# asbuilt.net
KiCad netlist of a schematic drawn in EAGLE
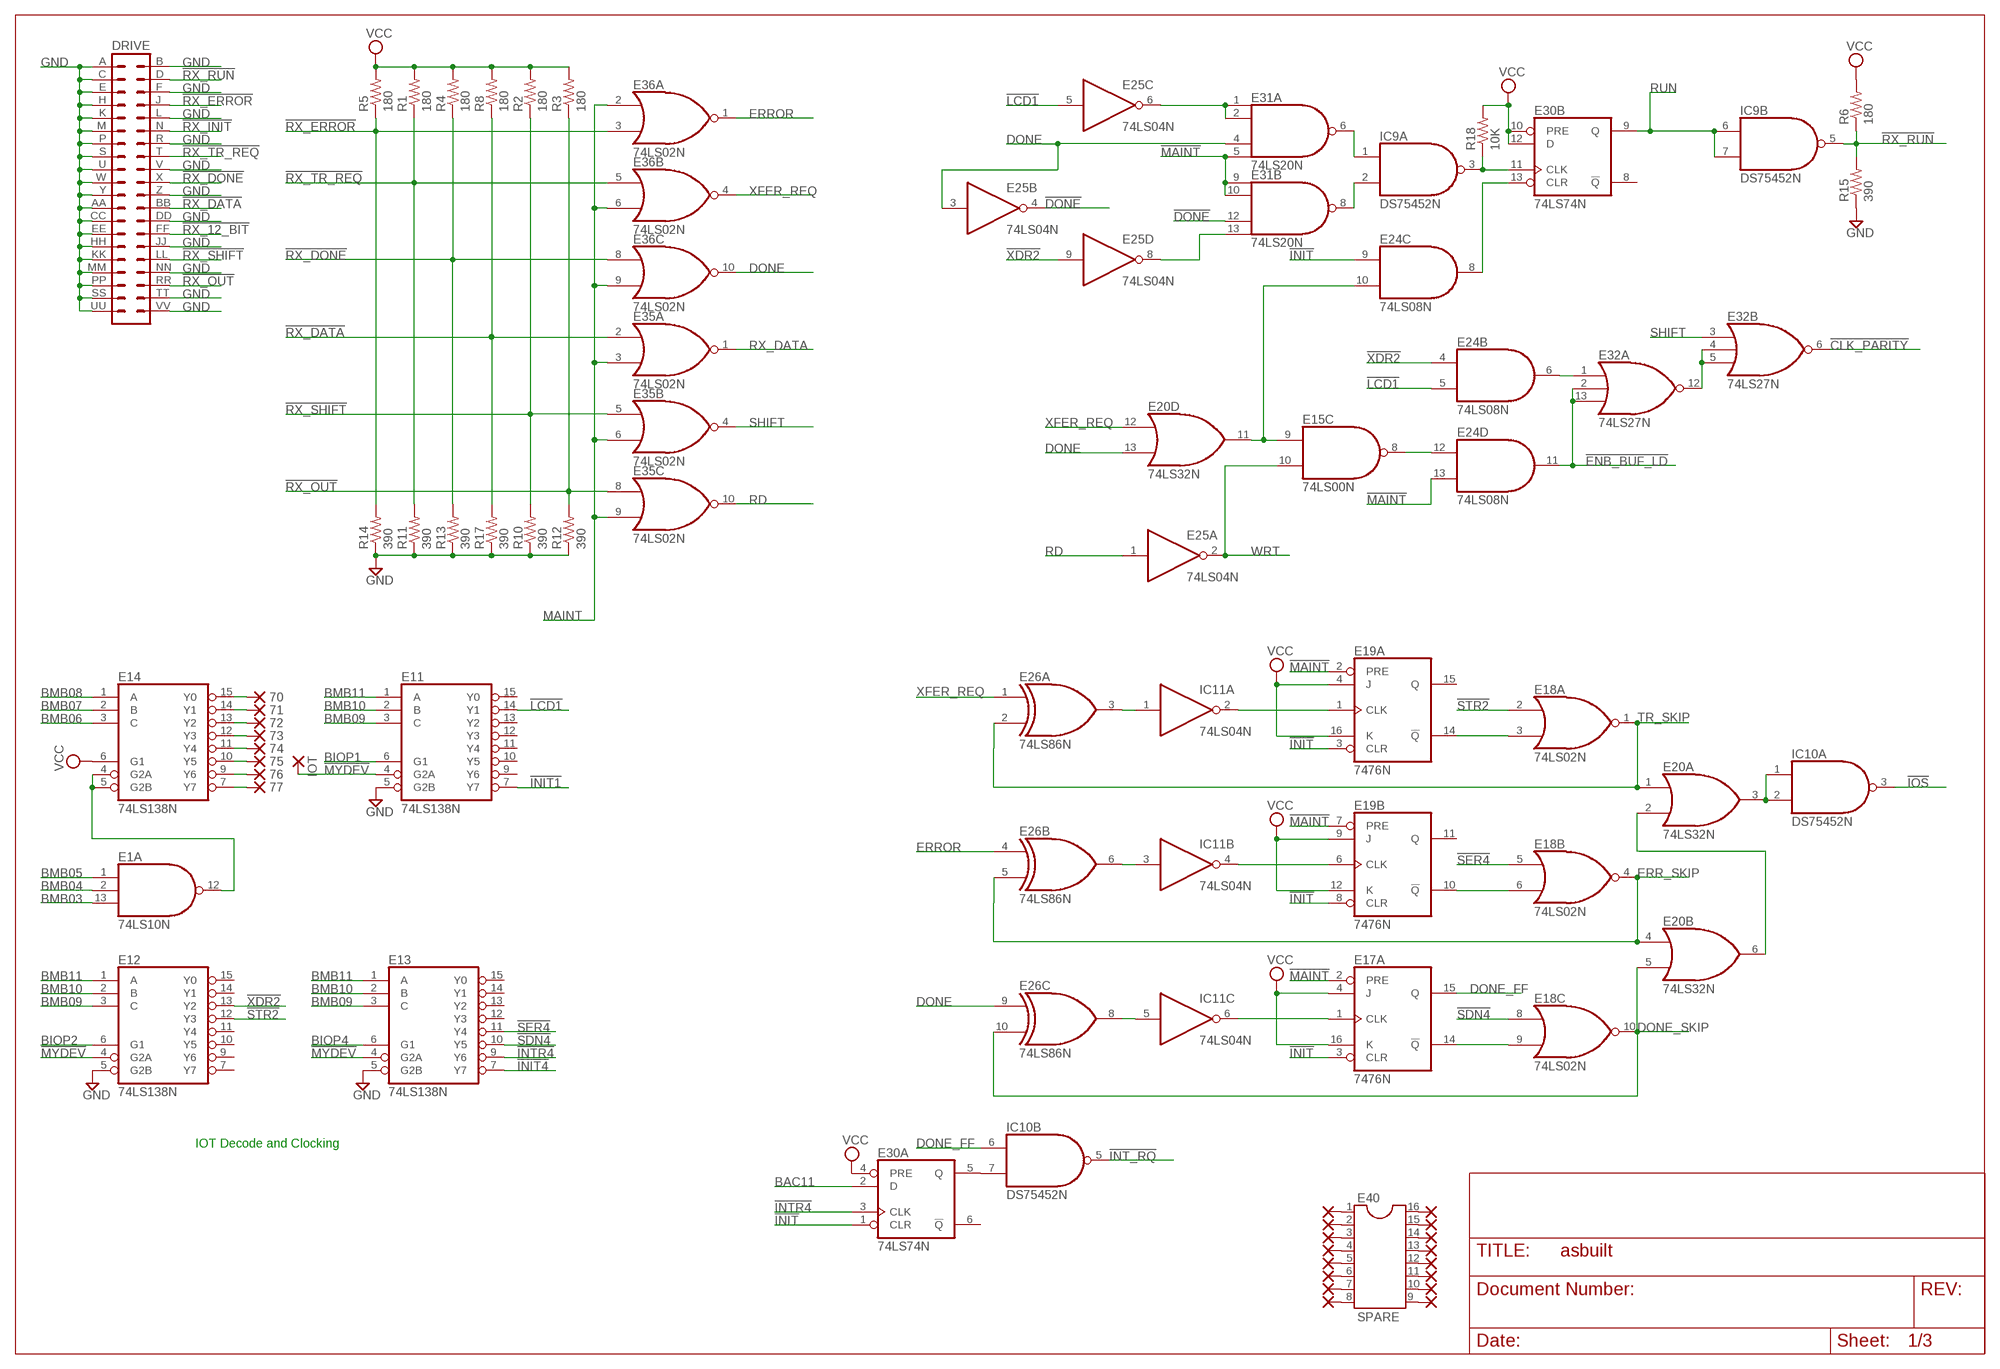
[diagram p0: schematic, sheet 1]
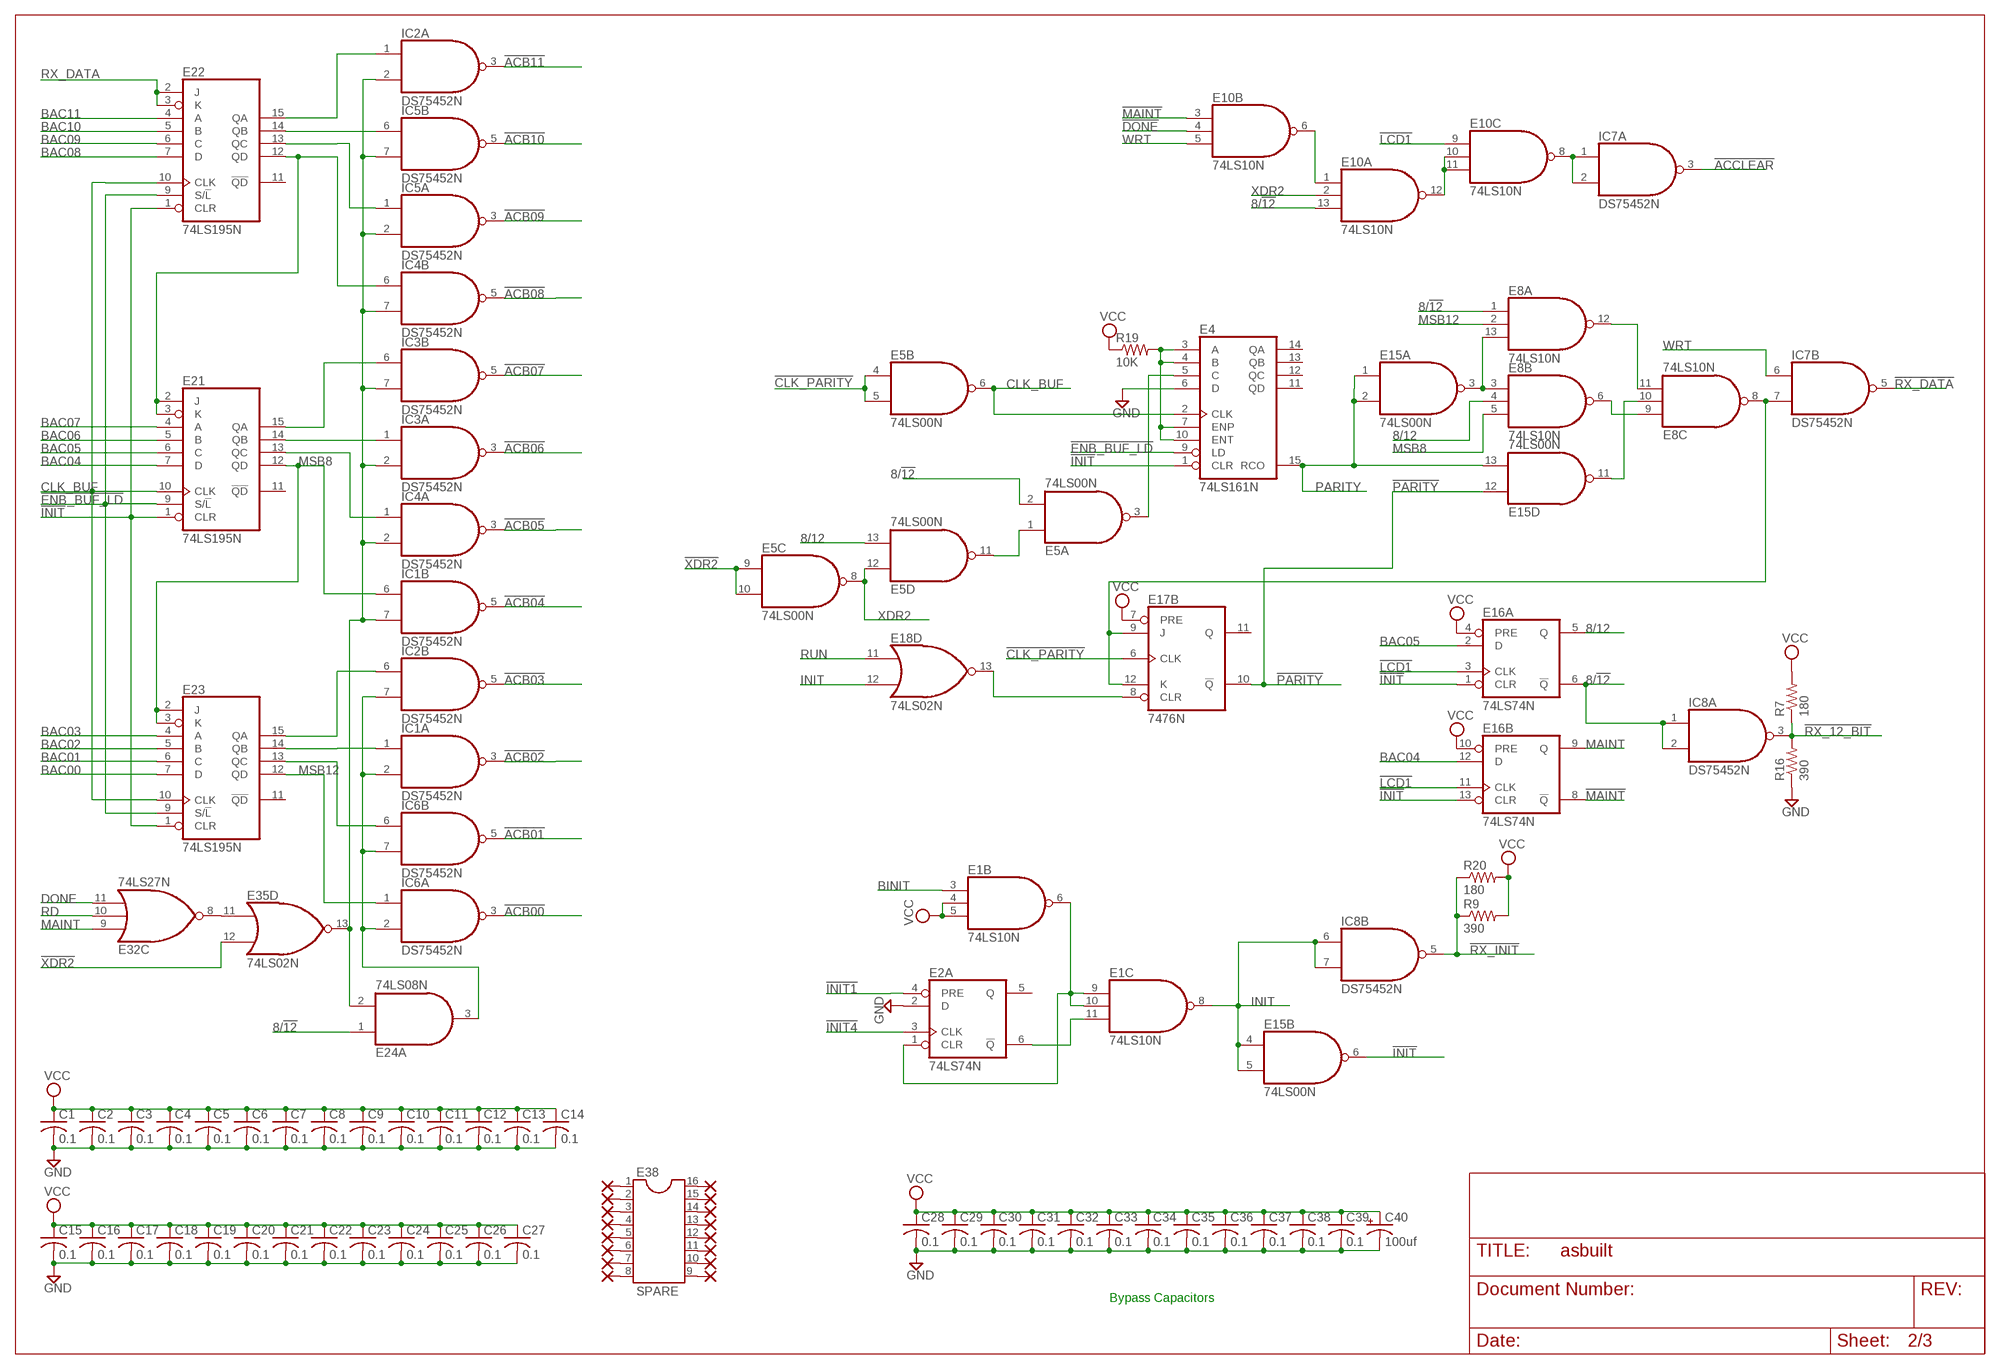
[diagram p1: schematic, sheet 2]
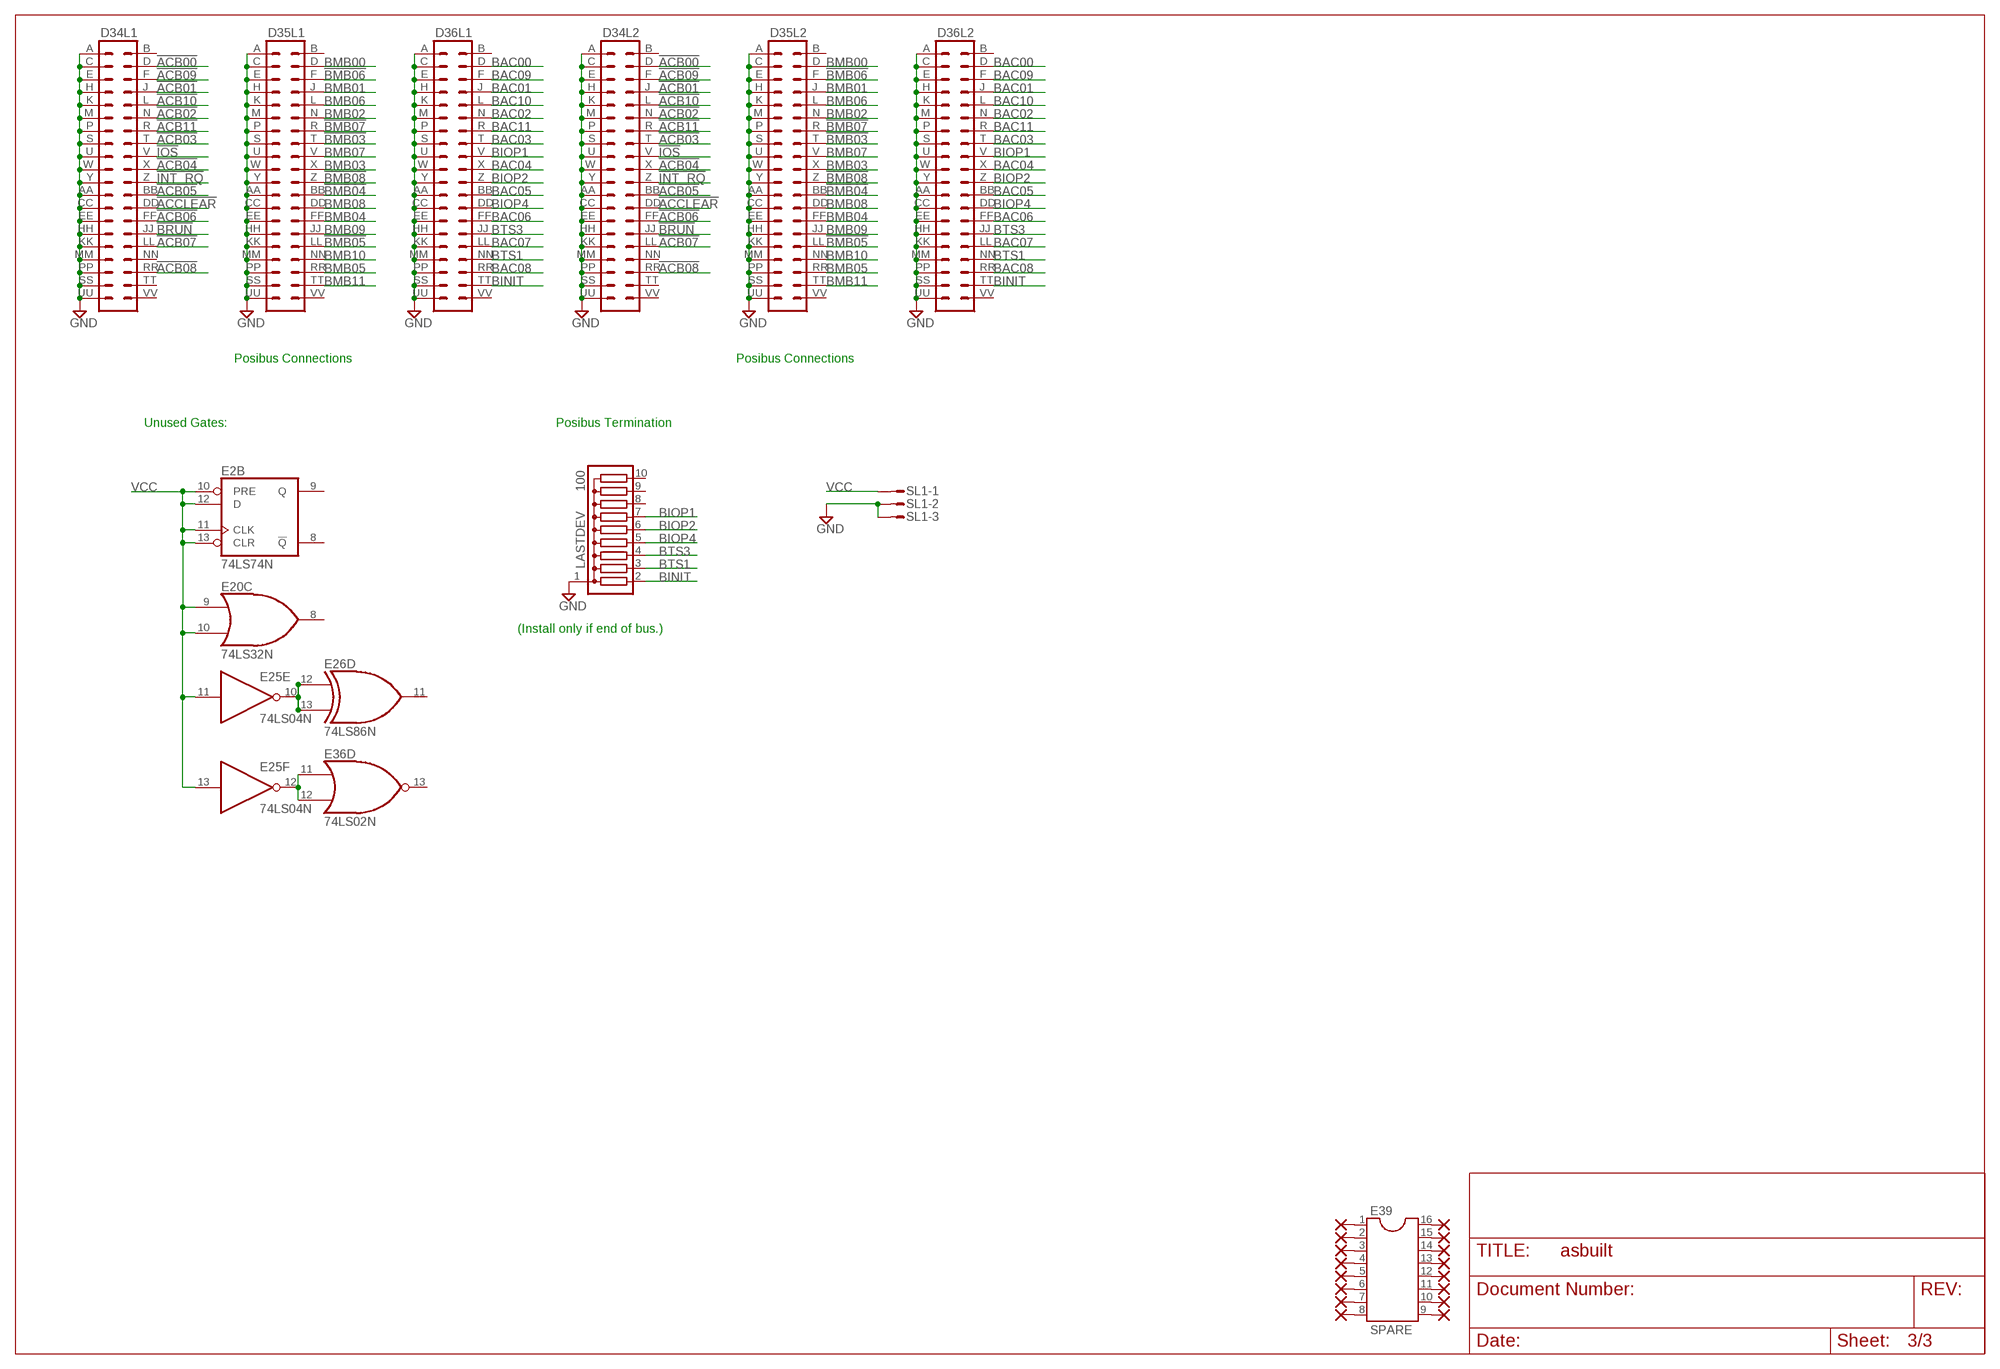
[diagram p2: schematic, sheet 3]

(export (version "E")
  (design (tool "Eeschema 10.0.6"))
  (components
    (comp (ref "C1")
      (value "0.1")
      (footprint "eagle-import:C050-025X075")
      (libsource (lib "eagle-import") (part "C-US050-025X075"))
    )
    (comp (ref "C2")
      (value "0.1")
      (footprint "eagle-import:C050-025X075")
      (libsource (lib "eagle-import") (part "C-US050-025X075"))
    )
    (comp (ref "C3")
      (value "0.1")
      (footprint "eagle-import:C050-025X075")
      (libsource (lib "eagle-import") (part "C-US050-025X075"))
    )
    (comp (ref "C4")
      (value "0.1")
      (footprint "eagle-import:C050-025X075")
      (libsource (lib "eagle-import") (part "C-US050-025X075"))
    )
    (comp (ref "C5")
      (value "0.1")
      (footprint "eagle-import:C050-025X075")
      (libsource (lib "eagle-import") (part "C-US050-025X075"))
    )
    (comp (ref "C6")
      (value "0.1")
      (footprint "eagle-import:C050-025X075")
      (libsource (lib "eagle-import") (part "C-US050-025X075"))
    )
    (comp (ref "C7")
      (value "0.1")
      (footprint "eagle-import:C050-025X075")
      (libsource (lib "eagle-import") (part "C-US050-025X075"))
    )
    (comp (ref "C8")
      (value "0.1")
      (footprint "eagle-import:C050-025X075")
      (libsource (lib "eagle-import") (part "C-US050-025X075"))
    )
    (comp (ref "C9")
      (value "0.1")
      (footprint "eagle-import:C050-025X075")
      (libsource (lib "eagle-import") (part "C-US050-025X075"))
    )
    (comp (ref "C10")
      (value "0.1")
      (footprint "eagle-import:C050-025X075")
      (libsource (lib "eagle-import") (part "C-US050-025X075"))
    )
    (comp (ref "C11")
      (value "0.1")
      (footprint "eagle-import:C050-025X075")
      (libsource (lib "eagle-import") (part "C-US050-025X075"))
    )
    (comp (ref "C12")
      (value "0.1")
      (footprint "eagle-import:C050-025X075")
      (libsource (lib "eagle-import") (part "C-US050-025X075"))
    )
    (comp (ref "C13")
      (value "0.1")
      (footprint "eagle-import:C050-025X075")
      (libsource (lib "eagle-import") (part "C-US050-025X075"))
    )
    (comp (ref "C14")
      (value "0.1")
      (footprint "eagle-import:C050-025X075")
      (libsource (lib "eagle-import") (part "C-US050-025X075"))
    )
    (comp (ref "C15")
      (value "0.1")
      (footprint "eagle-import:C050-025X075")
      (libsource (lib "eagle-import") (part "C-US050-025X075"))
    )
    (comp (ref "C16")
      (value "0.1")
      (footprint "eagle-import:C050-025X075")
      (libsource (lib "eagle-import") (part "C-US050-025X075"))
    )
    (comp (ref "C17")
      (value "0.1")
      (footprint "eagle-import:C050-025X075")
      (libsource (lib "eagle-import") (part "C-US050-025X075"))
    )
    (comp (ref "C18")
      (value "0.1")
      (footprint "eagle-import:C050-025X075")
      (libsource (lib "eagle-import") (part "C-US050-025X075"))
    )
    (comp (ref "C19")
      (value "0.1")
      (footprint "eagle-import:C050-025X075")
      (libsource (lib "eagle-import") (part "C-US050-025X075"))
    )
    (comp (ref "C20")
      (value "0.1")
      (footprint "eagle-import:C050-025X075")
      (libsource (lib "eagle-import") (part "C-US050-025X075"))
    )
    (comp (ref "C21")
      (value "0.1")
      (footprint "eagle-import:C050-025X075")
      (libsource (lib "eagle-import") (part "C-US050-025X075"))
    )
    (comp (ref "C22")
      (value "0.1")
      (footprint "eagle-import:C050-025X075")
      (libsource (lib "eagle-import") (part "C-US050-025X075"))
    )
    (comp (ref "C23")
      (value "0.1")
      (footprint "eagle-import:C050-025X075")
      (libsource (lib "eagle-import") (part "C-US050-025X075"))
    )
    (comp (ref "C24")
      (value "0.1")
      (footprint "eagle-import:C050-025X075")
      (libsource (lib "eagle-import") (part "C-US050-025X075"))
    )
    (comp (ref "C25")
      (value "0.1")
      (footprint "eagle-import:C050-025X075")
      (libsource (lib "eagle-import") (part "C-US050-025X075"))
    )
    (comp (ref "C26")
      (value "0.1")
      (footprint "eagle-import:C050-025X075")
      (libsource (lib "eagle-import") (part "C-US050-025X075"))
    )
    (comp (ref "C27")
      (value "0.1")
      (footprint "eagle-import:C050-025X075")
      (libsource (lib "eagle-import") (part "C-US050-025X075"))
    )
    (comp (ref "C28")
      (value "0.1")
      (footprint "eagle-import:C050-025X075")
      (libsource (lib "eagle-import") (part "C-US050-025X075"))
    )
    (comp (ref "C29")
      (value "0.1")
      (footprint "eagle-import:C050-025X075")
      (libsource (lib "eagle-import") (part "C-US050-025X075"))
    )
    (comp (ref "C30")
      (value "0.1")
      (footprint "eagle-import:C050-025X075")
      (libsource (lib "eagle-import") (part "C-US050-025X075"))
    )
    (comp (ref "C31")
      (value "0.1")
      (footprint "eagle-import:C050-025X075")
      (libsource (lib "eagle-import") (part "C-US050-025X075"))
    )
    (comp (ref "C32")
      (value "0.1")
      (footprint "eagle-import:C050-025X075")
      (libsource (lib "eagle-import") (part "C-US050-025X075"))
    )
    (comp (ref "C33")
      (value "0.1")
      (footprint "eagle-import:C050-025X075")
      (libsource (lib "eagle-import") (part "C-US050-025X075"))
    )
    (comp (ref "C34")
      (value "0.1")
      (footprint "eagle-import:C050-025X075")
      (libsource (lib "eagle-import") (part "C-US050-025X075"))
    )
    (comp (ref "C35")
      (value "0.1")
      (footprint "eagle-import:C050-025X075")
      (libsource (lib "eagle-import") (part "C-US050-025X075"))
    )
    (comp (ref "C36")
      (value "0.1")
      (footprint "eagle-import:C050-025X075")
      (libsource (lib "eagle-import") (part "C-US050-025X075"))
    )
    (comp (ref "C37")
      (value "0.1")
      (footprint "eagle-import:C050-025X075")
      (libsource (lib "eagle-import") (part "C-US050-025X075"))
    )
    (comp (ref "C38")
      (value "0.1")
      (footprint "eagle-import:C050-025X075")
      (libsource (lib "eagle-import") (part "C-US050-025X075"))
    )
    (comp (ref "C39")
      (value "0.1")
      (footprint "eagle-import:C050-025X075")
      (libsource (lib "eagle-import") (part "C-US050-025X075"))
    )
    (comp (ref "C40")
      (value "100uf")
      (footprint "eagle-import:E22-9")
      (libsource (lib "eagle-import") (part "CPOL-USE22-9AXIAL"))
    )
    (comp (ref "E1")
      (value "74LS10N")
      (footprint "eagle-import:DIL14")
      (libsource (lib "eagle-import") (part "7410NLS"))
    )
    (comp (ref "E2")
      (value "74LS74N")
      (footprint "eagle-import:DIL14")
      (libsource (lib "eagle-import") (part "7474NLS"))
    )
    (comp (ref "E4")
      (value "74LS161N")
      (footprint "eagle-import:DIL16")
      (libsource (lib "eagle-import") (part "74161NLS"))
    )
    (comp (ref "E5")
      (value "74LS00N")
      (footprint "eagle-import:DIL14")
      (libsource (lib "eagle-import") (part "7400NLS"))
    )
    (comp (ref "E8")
      (value "74LS10N")
      (footprint "eagle-import:DIL14")
      (libsource (lib "eagle-import") (part "7410NLS"))
    )
    (comp (ref "E10")
      (value "74LS10N")
      (footprint "eagle-import:DIL14")
      (libsource (lib "eagle-import") (part "7410NLS"))
    )
    (comp (ref "E15")
      (value "74LS00N")
      (footprint "eagle-import:DIL14")
      (libsource (lib "eagle-import") (part "7400NLS"))
    )
    (comp (ref "E16")
      (value "74LS74N")
      (footprint "eagle-import:DIL14")
      (libsource (lib "eagle-import") (part "7474NLS"))
    )
    (comp (ref "E17")
      (value "7476N")
      (footprint "eagle-import:DIL16")
      (libsource (lib "eagle-import") (part "7476N"))
    )
    (comp (ref "E18")
      (value "74LS02N")
      (footprint "eagle-import:DIL14")
      (libsource (lib "eagle-import") (part "7402NLS"))
    )
    (comp (ref "E21")
      (value "74LS195N")
      (footprint "eagle-import:DIL16")
      (libsource (lib "eagle-import") (part "74195NLS"))
    )
    (comp (ref "E22")
      (value "74LS195N")
      (footprint "eagle-import:DIL16")
      (libsource (lib "eagle-import") (part "74195NLS"))
    )
    (comp (ref "E23")
      (value "74LS195N")
      (footprint "eagle-import:DIL16")
      (libsource (lib "eagle-import") (part "74195NLS"))
    )
    (comp (ref "E24")
      (value "74LS08N")
      (footprint "eagle-import:DIL14")
      (libsource (lib "eagle-import") (part "7408NLS"))
    )
    (comp (ref "E32")
      (value "74LS27N")
      (footprint "eagle-import:DIL14")
      (libsource (lib "eagle-import") (part "7427NLS"))
    )
    (comp (ref "E35")
      (value "74LS02N")
      (footprint "eagle-import:DIL14")
      (libsource (lib "eagle-import") (part "7402NLS"))
    )
    (comp (ref "E38")
      (value "SPARE")
      (footprint "eagle-import:DIL16")
      (libsource (lib "eagle-import") (part "DIL16"))
    )
    (comp (ref "IC1")
      (value "DS75452N")
      (footprint "eagle-import:DIL08")
      (libsource (lib "eagle-import") (part "DS75452N"))
    )
    (comp (ref "IC2")
      (value "DS75452N")
      (footprint "eagle-import:DIL08")
      (libsource (lib "eagle-import") (part "DS75452N"))
    )
    (comp (ref "IC3")
      (value "DS75452N")
      (footprint "eagle-import:DIL08")
      (libsource (lib "eagle-import") (part "DS75452N"))
    )
    (comp (ref "IC4")
      (value "DS75452N")
      (footprint "eagle-import:DIL08")
      (libsource (lib "eagle-import") (part "DS75452N"))
    )
    (comp (ref "IC5")
      (value "DS75452N")
      (footprint "eagle-import:DIL08")
      (libsource (lib "eagle-import") (part "DS75452N"))
    )
    (comp (ref "IC6")
      (value "DS75452N")
      (footprint "eagle-import:DIL08")
      (libsource (lib "eagle-import") (part "DS75452N"))
    )
    (comp (ref "IC7")
      (value "DS75452N")
      (footprint "eagle-import:DIL08")
      (libsource (lib "eagle-import") (part "DS75452N"))
    )
    (comp (ref "IC8")
      (value "DS75452N")
      (footprint "eagle-import:DIL08")
      (libsource (lib "eagle-import") (part "DS75452N"))
    )
    (comp (ref "PAD10")
      (value "1,6/0,8")
      (footprint "eagle-import:1,6_0,8")
      (libsource (lib "eagle-import") (part "1,6/0,8"))
    )
    (comp (ref "PAD11")
      (value "1,6/0,8")
      (footprint "eagle-import:1,6_0,8")
      (libsource (lib "eagle-import") (part "1,6/0,8"))
    )
    (comp (ref "PAD12")
      (value "1,6/0,8")
      (footprint "eagle-import:1,6_0,8")
      (libsource (lib "eagle-import") (part "1,6/0,8"))
    )
    (comp (ref "PAD13")
      (value "1,6/0,8")
      (footprint "eagle-import:1,6_0,8")
      (libsource (lib "eagle-import") (part "1,6/0,8"))
    )
    (comp (ref "PAD14")
      (value "1,6/0,8")
      (footprint "eagle-import:1,6_0,8")
      (libsource (lib "eagle-import") (part "1,6/0,8"))
    )
    (comp (ref "PAD15")
      (value "1,6/0,8")
      (footprint "eagle-import:1,6_0,8")
      (libsource (lib "eagle-import") (part "1,6/0,8"))
    )
    (comp (ref "PAD16")
      (value "1,6/0,8")
      (footprint "eagle-import:1,6_0,8")
      (libsource (lib "eagle-import") (part "1,6/0,8"))
    )
    (comp (ref "PAD17")
      (value "1,6/0,8")
      (footprint "eagle-import:1,6_0,8")
      (libsource (lib "eagle-import") (part "1,6/0,8"))
    )
    (comp (ref "PAD20")
      (value "1,6/0,8")
      (footprint "eagle-import:1,6_0,8")
      (libsource (lib "eagle-import") (part "1,6/0,8"))
    )
    (comp (ref "PAD21")
      (value "1,6/0,8")
      (footprint "eagle-import:1,6_0,8")
      (libsource (lib "eagle-import") (part "1,6/0,8"))
    )
    (comp (ref "PAD22")
      (value "1,6/0,8")
      (footprint "eagle-import:1,6_0,8")
      (libsource (lib "eagle-import") (part "1,6/0,8"))
    )
    (comp (ref "PAD23")
      (value "1,6/0,8")
      (footprint "eagle-import:1,6_0,8")
      (libsource (lib "eagle-import") (part "1,6/0,8"))
    )
    (comp (ref "PAD24")
      (value "1,6/0,8")
      (footprint "eagle-import:1,6_0,8")
      (libsource (lib "eagle-import") (part "1,6/0,8"))
    )
    (comp (ref "PAD25")
      (value "1,6/0,8")
      (footprint "eagle-import:1,6_0,8")
      (libsource (lib "eagle-import") (part "1,6/0,8"))
    )
    (comp (ref "PAD26")
      (value "1,6/0,8")
      (footprint "eagle-import:1,6_0,8")
      (libsource (lib "eagle-import") (part "1,6/0,8"))
    )
    (comp (ref "PAD27")
      (value "1,6/0,8")
      (footprint "eagle-import:1,6_0,8")
      (libsource (lib "eagle-import") (part "1,6/0,8"))
    )
    (comp (ref "R7")
      (value "180")
      (footprint "eagle-import:0207_10")
      (libsource (lib "eagle-import") (part "R-US_0207/10"))
    )
    (comp (ref "R9")
      (value "390")
      (footprint "eagle-import:0207_10")
      (libsource (lib "eagle-import") (part "R-US_0207/10"))
    )
    (comp (ref "R16")
      (value "390")
      (footprint "eagle-import:0207_10")
      (libsource (lib "eagle-import") (part "R-US_0207/10"))
    )
    (comp (ref "R19")
      (value "10K")
      (footprint "eagle-import:0207_10")
      (libsource (lib "eagle-import") (part "R-US_0207/10"))
    )
    (comp (ref "R20")
      (value "180")
      (footprint "eagle-import:0207_10")
      (libsource (lib "eagle-import") (part "R-US_0207/10"))
    )
    (comp (ref "D34L1")
      (value "DEC40PINV")
      (footprint "eagle-import:DEC40PINV")
      (libsource (lib "eagle-import") (part "DEC40PINV"))
    )
    (comp (ref "D34L2")
      (value "DEC40PINV")
      (footprint "eagle-import:DEC40PINV")
      (libsource (lib "eagle-import") (part "DEC40PINV"))
    )
    (comp (ref "D35L1")
      (value "DEC40PINV")
      (footprint "eagle-import:DEC40PINV")
      (libsource (lib "eagle-import") (part "DEC40PINV"))
    )
    (comp (ref "D35L2")
      (value "DEC40PINV")
      (footprint "eagle-import:DEC40PINV")
      (libsource (lib "eagle-import") (part "DEC40PINV"))
    )
    (comp (ref "D36L1")
      (value "DEC40PINV")
      (footprint "eagle-import:DEC40PINV")
      (libsource (lib "eagle-import") (part "DEC40PINV"))
    )
    (comp (ref "D36L2")
      (value "DEC40PINV")
      (footprint "eagle-import:DEC40PINV")
      (libsource (lib "eagle-import") (part "DEC40PINV"))
    )
    (comp (ref "E20")
      (value "74LS32N")
      (footprint "eagle-import:DIL14")
      (libsource (lib "eagle-import") (part "7432NLS"))
    )
    (comp (ref "E25")
      (value "74LS04N")
      (footprint "eagle-import:DIL14")
      (libsource (lib "eagle-import") (part "7404NLS"))
    )
    (comp (ref "E26")
      (value "74LS86N")
      (footprint "eagle-import:DIL14")
      (libsource (lib "eagle-import") (part "7486NLS"))
    )
    (comp (ref "E36")
      (value "74LS02N")
      (footprint "eagle-import:DIL14")
      (libsource (lib "eagle-import") (part "7402NLS"))
    )
    (comp (ref "E39")
      (value "SPARE")
      (footprint "eagle-import:DIL16")
      (libsource (lib "eagle-import") (part "DIL16"))
    )
    (comp (ref "LASTDEV")
      (value "100")
      (footprint "eagle-import:SIL10")
      (libsource (lib "eagle-import") (part "G09R"))
    )
    (comp (ref "PAD42")
      (value "1,6/0,8")
      (footprint "eagle-import:1,6_0,8")
      (libsource (lib "eagle-import") (part "1,6/0,8"))
    )
    (comp (ref "PAD43")
      (value "1,6/0,8")
      (footprint "eagle-import:1,6_0,8")
      (libsource (lib "eagle-import") (part "1,6/0,8"))
    )
    (comp (ref "PAD44")
      (value "1,6/0,8")
      (footprint "eagle-import:1,6_0,8")
      (libsource (lib "eagle-import") (part "1,6/0,8"))
    )
    (comp (ref "PAD45")
      (value "1,6/0,8")
      (footprint "eagle-import:1,6_0,8")
      (libsource (lib "eagle-import") (part "1,6/0,8"))
    )
    (comp (ref "PAD46")
      (value "1,6/0,8")
      (footprint "eagle-import:1,6_0,8")
      (libsource (lib "eagle-import") (part "1,6/0,8"))
    )
    (comp (ref "PAD47")
      (value "1,6/0,8")
      (footprint "eagle-import:1,6_0,8")
      (libsource (lib "eagle-import") (part "1,6/0,8"))
    )
    (comp (ref "PAD48")
      (value "1,6/0,8")
      (footprint "eagle-import:1,6_0,8")
      (libsource (lib "eagle-import") (part "1,6/0,8"))
    )
    (comp (ref "PAD49")
      (value "1,6/0,8")
      (footprint "eagle-import:1,6_0,8")
      (libsource (lib "eagle-import") (part "1,6/0,8"))
    )
    (comp (ref "PAD50")
      (value "1,6/0,8")
      (footprint "eagle-import:1,6_0,8")
      (libsource (lib "eagle-import") (part "1,6/0,8"))
    )
    (comp (ref "PAD51")
      (value "1,6/0,8")
      (footprint "eagle-import:1,6_0,8")
      (libsource (lib "eagle-import") (part "1,6/0,8"))
    )
    (comp (ref "PAD52")
      (value "1,6/0,8")
      (footprint "eagle-import:1,6_0,8")
      (libsource (lib "eagle-import") (part "1,6/0,8"))
    )
    (comp (ref "PAD53")
      (value "1,6/0,8")
      (footprint "eagle-import:1,6_0,8")
      (libsource (lib "eagle-import") (part "1,6/0,8"))
    )
    (comp (ref "PAD54")
      (value "1,6/0,8")
      (footprint "eagle-import:1,6_0,8")
      (libsource (lib "eagle-import") (part "1,6/0,8"))
    )
    (comp (ref "PAD55")
      (value "1,6/0,8")
      (footprint "eagle-import:1,6_0,8")
      (libsource (lib "eagle-import") (part "1,6/0,8"))
    )
    (comp (ref "PAD56")
      (value "1,6/0,8")
      (footprint "eagle-import:1,6_0,8")
      (libsource (lib "eagle-import") (part "1,6/0,8"))
    )
    (comp (ref "PAD57")
      (value "1,6/0,8")
      (footprint "eagle-import:1,6_0,8")
      (libsource (lib "eagle-import") (part "1,6/0,8"))
    )
    (comp (ref "SL1")
      (value "MA04S")
      (footprint "eagle-import:04PA")
      (libsource (lib "eagle-import") (part "MA04S"))
    )
    (comp (ref "70")
      (value "1,6/0,8")
      (footprint "eagle-import:1,6_0,8")
      (libsource (lib "eagle-import") (part "1,6/0,8"))
    )
    (comp (ref "71")
      (value "1,6/0,8")
      (footprint "eagle-import:1,6_0,8")
      (libsource (lib "eagle-import") (part "1,6/0,8"))
    )
    (comp (ref "72")
      (value "1,6/0,8")
      (footprint "eagle-import:1,6_0,8")
      (libsource (lib "eagle-import") (part "1,6/0,8"))
    )
    (comp (ref "73")
      (value "1,6/0,8")
      (footprint "eagle-import:1,6_0,8")
      (libsource (lib "eagle-import") (part "1,6/0,8"))
    )
    (comp (ref "74")
      (value "1,6/0,8")
      (footprint "eagle-import:1,6_0,8")
      (libsource (lib "eagle-import") (part "1,6/0,8"))
    )
    (comp (ref "75")
      (value "1,6/0,8")
      (footprint "eagle-import:1,6_0,8")
      (libsource (lib "eagle-import") (part "1,6/0,8"))
    )
    (comp (ref "76")
      (value "1,6/0,8")
      (footprint "eagle-import:1,6_0,8")
      (libsource (lib "eagle-import") (part "1,6/0,8"))
    )
    (comp (ref "77")
      (value "1,6/0,8")
      (footprint "eagle-import:1,6_0,8")
      (libsource (lib "eagle-import") (part "1,6/0,8"))
    )
    (comp (ref "DRIVE")
      (value "DEC40PINV")
      (footprint "eagle-import:DEC40PINV")
      (libsource (lib "eagle-import") (part "DEC40PINV"))
    )
    (comp (ref "E11")
      (value "74LS138N")
      (footprint "eagle-import:DIL16")
      (libsource (lib "eagle-import") (part "74138NLS"))
    )
    (comp (ref "E12")
      (value "74LS138N")
      (footprint "eagle-import:DIL16")
      (libsource (lib "eagle-import") (part "74138NLS"))
    )
    (comp (ref "E13")
      (value "74LS138N")
      (footprint "eagle-import:DIL16")
      (libsource (lib "eagle-import") (part "74138NLS"))
    )
    (comp (ref "E14")
      (value "74LS138N")
      (footprint "eagle-import:DIL16")
      (libsource (lib "eagle-import") (part "74138NLS"))
    )
    (comp (ref "E19")
      (value "7476N")
      (footprint "eagle-import:DIL16")
      (libsource (lib "eagle-import") (part "7476N"))
    )
    (comp (ref "E30")
      (value "74LS74N")
      (footprint "eagle-import:DIL14")
      (libsource (lib "eagle-import") (part "7474NLS"))
    )
    (comp (ref "E31")
      (value "74LS20N")
      (footprint "eagle-import:DIL14")
      (libsource (lib "eagle-import") (part "7420NLS"))
    )
    (comp (ref "E40")
      (value "SPARE")
      (footprint "eagle-import:DIL16")
      (libsource (lib "eagle-import") (part "DIL16"))
    )
    (comp (ref "IC9")
      (value "DS75452N")
      (footprint "eagle-import:DIL08")
      (libsource (lib "eagle-import") (part "DS75452N"))
    )
    (comp (ref "IC10")
      (value "DS75452N")
      (footprint "eagle-import:DIL08")
      (libsource (lib "eagle-import") (part "DS75452N"))
    )
    (comp (ref "IC11")
      (value "74LS04N")
      (footprint "eagle-import:DIL14")
      (libsource (lib "eagle-import") (part "7404NLS"))
    )
    (comp (ref "IOT")
      (value "1,6/0,8")
      (footprint "eagle-import:1,6_0,8")
      (libsource (lib "eagle-import") (part "1,6/0,8"))
    )
    (comp (ref "PAD18")
      (value "1,6/0,8")
      (footprint "eagle-import:1,6_0,8")
      (libsource (lib "eagle-import") (part "1,6/0,8"))
    )
    (comp (ref "PAD19")
      (value "1,6/0,8")
      (footprint "eagle-import:1,6_0,8")
      (libsource (lib "eagle-import") (part "1,6/0,8"))
    )
    (comp (ref "PAD28")
      (value "1,6/0,8")
      (footprint "eagle-import:1,6_0,8")
      (libsource (lib "eagle-import") (part "1,6/0,8"))
    )
    (comp (ref "PAD29")
      (value "1,6/0,8")
      (footprint "eagle-import:1,6_0,8")
      (libsource (lib "eagle-import") (part "1,6/0,8"))
    )
    (comp (ref "PAD30")
      (value "1,6/0,8")
      (footprint "eagle-import:1,6_0,8")
      (libsource (lib "eagle-import") (part "1,6/0,8"))
    )
    (comp (ref "PAD31")
      (value "1,6/0,8")
      (footprint "eagle-import:1,6_0,8")
      (libsource (lib "eagle-import") (part "1,6/0,8"))
    )
    (comp (ref "PAD32")
      (value "1,6/0,8")
      (footprint "eagle-import:1,6_0,8")
      (libsource (lib "eagle-import") (part "1,6/0,8"))
    )
    (comp (ref "PAD33")
      (value "1,6/0,8")
      (footprint "eagle-import:1,6_0,8")
      (libsource (lib "eagle-import") (part "1,6/0,8"))
    )
    (comp (ref "PAD34")
      (value "1,6/0,8")
      (footprint "eagle-import:1,6_0,8")
      (libsource (lib "eagle-import") (part "1,6/0,8"))
    )
    (comp (ref "PAD35")
      (value "1,6/0,8")
      (footprint "eagle-import:1,6_0,8")
      (libsource (lib "eagle-import") (part "1,6/0,8"))
    )
    (comp (ref "PAD36")
      (value "1,6/0,8")
      (footprint "eagle-import:1,6_0,8")
      (libsource (lib "eagle-import") (part "1,6/0,8"))
    )
    (comp (ref "PAD37")
      (value "1,6/0,8")
      (footprint "eagle-import:1,6_0,8")
      (libsource (lib "eagle-import") (part "1,6/0,8"))
    )
    (comp (ref "PAD38")
      (value "1,6/0,8")
      (footprint "eagle-import:1,6_0,8")
      (libsource (lib "eagle-import") (part "1,6/0,8"))
    )
    (comp (ref "PAD39")
      (value "1,6/0,8")
      (footprint "eagle-import:1,6_0,8")
      (libsource (lib "eagle-import") (part "1,6/0,8"))
    )
    (comp (ref "PAD40")
      (value "1,6/0,8")
      (footprint "eagle-import:1,6_0,8")
      (libsource (lib "eagle-import") (part "1,6/0,8"))
    )
    (comp (ref "PAD41")
      (value "1,6/0,8")
      (footprint "eagle-import:1,6_0,8")
      (libsource (lib "eagle-import") (part "1,6/0,8"))
    )
    (comp (ref "R1")
      (value "180")
      (footprint "eagle-import:0207_10")
      (libsource (lib "eagle-import") (part "R-US_0207/10"))
    )
    (comp (ref "R2")
      (value "180")
      (footprint "eagle-import:0207_10")
      (libsource (lib "eagle-import") (part "R-US_0207/10"))
    )
    (comp (ref "R3")
      (value "180")
      (footprint "eagle-import:0207_10")
      (libsource (lib "eagle-import") (part "R-US_0207/10"))
    )
    (comp (ref "R4")
      (value "180")
      (footprint "eagle-import:0207_10")
      (libsource (lib "eagle-import") (part "R-US_0207/10"))
    )
    (comp (ref "R5")
      (value "180")
      (footprint "eagle-import:0207_10")
      (libsource (lib "eagle-import") (part "R-US_0207/10"))
    )
    (comp (ref "R6")
      (value "180")
      (footprint "eagle-import:0207_10")
      (libsource (lib "eagle-import") (part "R-US_0207/10"))
    )
    (comp (ref "R8")
      (value "180")
      (footprint "eagle-import:0207_10")
      (libsource (lib "eagle-import") (part "R-US_0207/10"))
    )
    (comp (ref "R10")
      (value "390")
      (footprint "eagle-import:0207_10")
      (libsource (lib "eagle-import") (part "R-US_0207/10"))
    )
    (comp (ref "R11")
      (value "390")
      (footprint "eagle-import:0207_10")
      (libsource (lib "eagle-import") (part "R-US_0207/10"))
    )
    (comp (ref "R12")
      (value "390")
      (footprint "eagle-import:0207_10")
      (libsource (lib "eagle-import") (part "R-US_0207/10"))
    )
    (comp (ref "R13")
      (value "390")
      (footprint "eagle-import:0207_10")
      (libsource (lib "eagle-import") (part "R-US_0207/10"))
    )
    (comp (ref "R14")
      (value "390")
      (footprint "eagle-import:0207_10")
      (libsource (lib "eagle-import") (part "R-US_0207/10"))
    )
    (comp (ref "R15")
      (value "390")
      (footprint "eagle-import:0207_10")
      (libsource (lib "eagle-import") (part "R-US_0207/10"))
    )
    (comp (ref "R17")
      (value "390")
      (footprint "eagle-import:0207_10")
      (libsource (lib "eagle-import") (part "R-US_0207/10"))
    )
    (comp (ref "R18")
      (value "10K")
      (footprint "eagle-import:0207_10")
      (libsource (lib "eagle-import") (part "R-US_0207/10"))
    )
  )
  (nets
    (net (code "1") (name "8{slash}12") (class "Default")
      (node (ref "E16") (pin "5") (pinfunction "Q_5") (pintype "output"))
      (node (ref "E5") (pin "13") (pinfunction "I1_13") (pintype "input"))
      (node (ref "E8") (pin "4") (pinfunction "I1_4") (pintype "input"))
    )
    (net (code "2") (name "8{slash}~{12}") (class "Default")
      (node (ref "E10") (pin "13") (pinfunction "I2_13") (pintype "input"))
      (node (ref "E16") (pin "6") (pinfunction "~{Q}_6") (pintype "output"))
      (node (ref "E24") (pin "1") (pinfunction "I0_1") (pintype "input"))
      (node (ref "E5") (pin "2") (pinfunction "I1_2") (pintype "input"))
      (node (ref "E8") (pin "1") (pinfunction "I0_1") (pintype "input"))
      (node (ref "IC8") (pin "1") (pinfunction "I0_1") (pintype "input"))
      (node (ref "IC8") (pin "2") (pinfunction "I1_2") (pintype "input"))
    )
    (net (code "3") (name "BAC00") (class "Default")
      (node (ref "D36L1") (pin "D") (pinfunction "4_D") (pintype "bidirectional"))
      (node (ref "D36L2") (pin "D") (pinfunction "4_D") (pintype "bidirectional"))
      (node (ref "E23") (pin "7") (pinfunction "D_7") (pintype "input"))
    )
    (net (code "4") (name "BAC01") (class "Default")
      (node (ref "D36L1") (pin "J") (pinfunction "8_J") (pintype "bidirectional"))
      (node (ref "D36L2") (pin "J") (pinfunction "8_J") (pintype "bidirectional"))
      (node (ref "E23") (pin "6") (pinfunction "C_6") (pintype "input"))
    )
    (net (code "5") (name "BAC02") (class "Default")
      (node (ref "D36L1") (pin "N") (pinfunction "12_N") (pintype "bidirectional"))
      (node (ref "D36L2") (pin "N") (pinfunction "12_N") (pintype "bidirectional"))
      (node (ref "E23") (pin "5") (pinfunction "B_5") (pintype "input"))
    )
    (net (code "6") (name "BAC03") (class "Default")
      (node (ref "D36L1") (pin "T") (pinfunction "16_T") (pintype "bidirectional"))
      (node (ref "D36L2") (pin "T") (pinfunction "16_T") (pintype "bidirectional"))
      (node (ref "E23") (pin "4") (pinfunction "A_4") (pintype "input"))
    )
    (net (code "7") (name "BAC04") (class "Default")
      (node (ref "D36L1") (pin "X") (pinfunction "20_X") (pintype "bidirectional"))
      (node (ref "D36L2") (pin "X") (pinfunction "20_X") (pintype "bidirectional"))
      (node (ref "E16") (pin "12") (pinfunction "D_12") (pintype "input"))
      (node (ref "E21") (pin "7") (pinfunction "D_7") (pintype "input"))
    )
    (net (code "8") (name "BAC05") (class "Default")
      (node (ref "D36L1") (pin "BB") (pinfunction "24_BB") (pintype "bidirectional"))
      (node (ref "D36L2") (pin "BB") (pinfunction "24_BB") (pintype "bidirectional"))
      (node (ref "E16") (pin "2") (pinfunction "D_2") (pintype "input"))
      (node (ref "E21") (pin "6") (pinfunction "C_6") (pintype "input"))
    )
    (net (code "9") (name "BAC06") (class "Default")
      (node (ref "D36L1") (pin "FF") (pinfunction "28_FF") (pintype "bidirectional"))
      (node (ref "D36L2") (pin "FF") (pinfunction "28_FF") (pintype "bidirectional"))
      (node (ref "E21") (pin "5") (pinfunction "B_5") (pintype "input"))
    )
    (net (code "10") (name "BAC07") (class "Default")
      (node (ref "D36L1") (pin "LL") (pinfunction "32_LL") (pintype "bidirectional"))
      (node (ref "D36L2") (pin "LL") (pinfunction "32_LL") (pintype "bidirectional"))
      (node (ref "E21") (pin "4") (pinfunction "A_4") (pintype "input"))
    )
    (net (code "11") (name "BAC08") (class "Default")
      (node (ref "D36L1") (pin "RR") (pinfunction "36_RR") (pintype "bidirectional"))
      (node (ref "D36L2") (pin "RR") (pinfunction "36_RR") (pintype "bidirectional"))
      (node (ref "E22") (pin "7") (pinfunction "D_7") (pintype "input"))
    )
    (net (code "12") (name "BAC09") (class "Default")
      (node (ref "D36L1") (pin "F") (pinfunction "6_F") (pintype "bidirectional"))
      (node (ref "D36L2") (pin "F") (pinfunction "6_F") (pintype "bidirectional"))
      (node (ref "E22") (pin "6") (pinfunction "C_6") (pintype "input"))
    )
    (net (code "13") (name "BAC10") (class "Default")
      (node (ref "D36L1") (pin "L") (pinfunction "10_L") (pintype "bidirectional"))
      (node (ref "D36L2") (pin "L") (pinfunction "10_L") (pintype "bidirectional"))
      (node (ref "E22") (pin "5") (pinfunction "B_5") (pintype "input"))
    )
    (net (code "14") (name "BAC11") (class "Default")
      (node (ref "D36L1") (pin "R") (pinfunction "14_R") (pintype "bidirectional"))
      (node (ref "D36L2") (pin "R") (pinfunction "14_R") (pintype "bidirectional"))
      (node (ref "E22") (pin "4") (pinfunction "A_4") (pintype "input"))
      (node (ref "E30") (pin "2") (pinfunction "D_2") (pintype "input"))
    )
    (net (code "15") (name "BINIT") (class "Default")
      (node (ref "D36L1") (pin "TT") (pinfunction "38_TT") (pintype "bidirectional"))
      (node (ref "D36L2") (pin "TT") (pinfunction "38_TT") (pintype "bidirectional"))
      (node (ref "E1") (pin "3") (pinfunction "I0_3") (pintype "input"))
      (node (ref "LASTDEV") (pin "2") (pinfunction "2_2") (pintype "passive"))
    )
    (net (code "16") (name "BIOP1") (class "Default")
      (node (ref "D36L1") (pin "V") (pinfunction "18_V") (pintype "bidirectional"))
      (node (ref "D36L2") (pin "V") (pinfunction "18_V") (pintype "bidirectional"))
      (node (ref "E11") (pin "6") (pinfunction "G1_6") (pintype "input"))
      (node (ref "LASTDEV") (pin "7") (pinfunction "7_7") (pintype "passive"))
    )
    (net (code "17") (name "BIOP2") (class "Default")
      (node (ref "D36L1") (pin "Z") (pinfunction "22_Z") (pintype "bidirectional"))
      (node (ref "D36L2") (pin "Z") (pinfunction "22_Z") (pintype "bidirectional"))
      (node (ref "E12") (pin "6") (pinfunction "G1_6") (pintype "input"))
      (node (ref "LASTDEV") (pin "6") (pinfunction "6_6") (pintype "passive"))
    )
    (net (code "18") (name "BIOP4") (class "Default")
      (node (ref "D36L1") (pin "DD") (pinfunction "26_DD") (pintype "bidirectional"))
      (node (ref "D36L2") (pin "DD") (pinfunction "26_DD") (pintype "bidirectional"))
      (node (ref "E13") (pin "6") (pinfunction "G1_6") (pintype "input"))
      (node (ref "LASTDEV") (pin "5") (pinfunction "5_5") (pintype "passive"))
    )
    (net (code "19") (name "BMB00") (class "Default")
      (node (ref "D35L1") (pin "D") (pinfunction "4_D") (pintype "bidirectional"))
      (node (ref "D35L2") (pin "D") (pinfunction "4_D") (pintype "bidirectional"))
    )
    (net (code "20") (name "BMB01") (class "Default")
      (node (ref "D35L1") (pin "J") (pinfunction "8_J") (pintype "bidirectional"))
      (node (ref "D35L2") (pin "J") (pinfunction "8_J") (pintype "bidirectional"))
    )
    (net (code "21") (name "BMB02") (class "Default")
      (node (ref "D35L1") (pin "N") (pinfunction "12_N") (pintype "bidirectional"))
      (node (ref "D35L2") (pin "N") (pinfunction "12_N") (pintype "bidirectional"))
    )
    (net (code "22") (name "BMB03") (class "Default")
      (node (ref "D35L1") (pin "X") (pinfunction "20_X") (pintype "bidirectional"))
      (node (ref "D35L2") (pin "X") (pinfunction "20_X") (pintype "bidirectional"))
      (node (ref "E1") (pin "13") (pinfunction "I2_13") (pintype "input"))
    )
    (net (code "23") (name "BMB04") (class "Default")
      (node (ref "D35L1") (pin "FF") (pinfunction "28_FF") (pintype "bidirectional"))
      (node (ref "D35L2") (pin "FF") (pinfunction "28_FF") (pintype "bidirectional"))
      (node (ref "E1") (pin "2") (pinfunction "I1_2") (pintype "input"))
    )
    (net (code "24") (name "BMB05") (class "Default")
      (node (ref "D35L1") (pin "RR") (pinfunction "36_RR") (pintype "bidirectional"))
      (node (ref "D35L2") (pin "RR") (pinfunction "36_RR") (pintype "bidirectional"))
      (node (ref "E1") (pin "1") (pinfunction "I0_1") (pintype "input"))
    )
    (net (code "25") (name "BMB06") (class "Default")
      (node (ref "D35L1") (pin "L") (pinfunction "10_L") (pintype "bidirectional"))
      (node (ref "D35L2") (pin "L") (pinfunction "10_L") (pintype "bidirectional"))
      (node (ref "E14") (pin "3") (pinfunction "C_3") (pintype "input"))
    )
    (net (code "26") (name "BMB07") (class "Default")
      (node (ref "D35L1") (pin "V") (pinfunction "18_V") (pintype "bidirectional"))
      (node (ref "D35L2") (pin "V") (pinfunction "18_V") (pintype "bidirectional"))
      (node (ref "E14") (pin "2") (pinfunction "B_2") (pintype "input"))
    )
    (net (code "27") (name "BMB08") (class "Default")
      (node (ref "D35L1") (pin "DD") (pinfunction "26_DD") (pintype "bidirectional"))
      (node (ref "D35L2") (pin "DD") (pinfunction "26_DD") (pintype "bidirectional"))
      (node (ref "E14") (pin "1") (pinfunction "A_1") (pintype "input"))
    )
    (net (code "28") (name "BMB09") (class "Default")
      (node (ref "D35L1") (pin "JJ") (pinfunction "30_JJ") (pintype "bidirectional"))
      (node (ref "D35L2") (pin "JJ") (pinfunction "30_JJ") (pintype "bidirectional"))
      (node (ref "E11") (pin "3") (pinfunction "C_3") (pintype "input"))
      (node (ref "E12") (pin "3") (pinfunction "C_3") (pintype "input"))
      (node (ref "E13") (pin "3") (pinfunction "C_3") (pintype "input"))
    )
    (net (code "29") (name "BMB10") (class "Default")
      (node (ref "D35L1") (pin "NN") (pinfunction "34_NN") (pintype "bidirectional"))
      (node (ref "D35L2") (pin "NN") (pinfunction "34_NN") (pintype "bidirectional"))
      (node (ref "E11") (pin "2") (pinfunction "B_2") (pintype "input"))
      (node (ref "E12") (pin "2") (pinfunction "B_2") (pintype "input"))
      (node (ref "E13") (pin "2") (pinfunction "B_2") (pintype "input"))
    )
    (net (code "30") (name "BMB11") (class "Default")
      (node (ref "D35L1") (pin "TT") (pinfunction "38_TT") (pintype "bidirectional"))
      (node (ref "D35L2") (pin "TT") (pinfunction "38_TT") (pintype "bidirectional"))
      (node (ref "E11") (pin "1") (pinfunction "A_1") (pintype "input"))
      (node (ref "E12") (pin "1") (pinfunction "A_1") (pintype "input"))
      (node (ref "E13") (pin "1") (pinfunction "A_1") (pintype "input"))
    )
    (net (code "31") (name "BTS1") (class "Default")
      (node (ref "D36L1") (pin "NN") (pinfunction "34_NN") (pintype "bidirectional"))
      (node (ref "D36L2") (pin "NN") (pinfunction "34_NN") (pintype "bidirectional"))
      (node (ref "LASTDEV") (pin "3") (pinfunction "3_3") (pintype "passive"))
    )
    (net (code "32") (name "BTS3") (class "Default")
      (node (ref "D36L1") (pin "JJ") (pinfunction "30_JJ") (pintype "bidirectional"))
      (node (ref "D36L2") (pin "JJ") (pinfunction "30_JJ") (pintype "bidirectional"))
      (node (ref "LASTDEV") (pin "4") (pinfunction "4_4") (pintype "passive"))
    )
    (net (code "33") (name "CLK_BUF") (class "Default")
      (node (ref "E21") (pin "10") (pinfunction "CLK_10") (pintype "input"))
      (node (ref "E22") (pin "10") (pinfunction "CLK_10") (pintype "input"))
      (node (ref "E23") (pin "10") (pinfunction "CLK_10") (pintype "input"))
      (node (ref "E4") (pin "2") (pinfunction "CLK_2") (pintype "input"))
      (node (ref "E5") (pin "6") (pinfunction "O_6") (pintype "output"))
    )
    (net (code "34") (name "DONE") (class "Default")
      (node (ref "E20") (pin "13") (pinfunction "I1_13") (pintype "input"))
      (node (ref "E25") (pin "3") (pinfunction "I_3") (pintype "input"))
      (node (ref "E26") (pin "9") (pinfunction "I0_9") (pintype "input"))
      (node (ref "E31") (pin "4") (pinfunction "I2_4") (pintype "input"))
      (node (ref "E32") (pin "11") (pinfunction "I2_11") (pintype "input"))
      (node (ref "E36") (pin "10") (pinfunction "O_10") (pintype "output"))
    )
    (net (code "35") (name "DONE_FF") (class "Default")
      (node (ref "E17") (pin "15") (pinfunction "Q_15") (pintype "output"))
      (node (ref "IC10") (pin "6") (pinfunction "I0_6") (pintype "input"))
    )
    (net (code "36") (name "DONE_SKIP") (class "Default")
      (node (ref "E18") (pin "10") (pinfunction "O_10") (pintype "output"))
      (node (ref "E20") (pin "5") (pinfunction "I1_5") (pintype "input"))
      (node (ref "E26") (pin "10") (pinfunction "I1_10") (pintype "input"))
    )
    (net (code "37") (name "ERROR") (class "Default")
      (node (ref "E26") (pin "4") (pinfunction "I0_4") (pintype "input"))
      (node (ref "E36") (pin "1") (pinfunction "O_1") (pintype "output"))
    )
    (net (code "38") (name "ERR_SKIP") (class "Default")
      (node (ref "E18") (pin "4") (pinfunction "O_4") (pintype "output"))
      (node (ref "E20") (pin "4") (pinfunction "I0_4") (pintype "input"))
      (node (ref "E26") (pin "5") (pinfunction "I1_5") (pintype "input"))
    )
    (net (code "39") (name "GND") (class "Default")
      (node (ref "C1") (pin "2") (pinfunction "2_2") (pintype "passive"))
      (node (ref "C10") (pin "2") (pinfunction "2_2") (pintype "passive"))
      (node (ref "C11") (pin "2") (pinfunction "2_2") (pintype "passive"))
      (node (ref "C12") (pin "2") (pinfunction "2_2") (pintype "passive"))
      (node (ref "C13") (pin "2") (pinfunction "2_2") (pintype "passive"))
      (node (ref "C14") (pin "2") (pinfunction "2_2") (pintype "passive"))
      (node (ref "C15") (pin "2") (pinfunction "2_2") (pintype "passive"))
      (node (ref "C16") (pin "2") (pinfunction "2_2") (pintype "passive"))
      (node (ref "C17") (pin "2") (pinfunction "2_2") (pintype "passive"))
      (node (ref "C18") (pin "2") (pinfunction "2_2") (pintype "passive"))
      (node (ref "C19") (pin "2") (pinfunction "2_2") (pintype "passive"))
      (node (ref "C2") (pin "2") (pinfunction "2_2") (pintype "passive"))
      (node (ref "C20") (pin "2") (pinfunction "2_2") (pintype "passive"))
      (node (ref "C21") (pin "2") (pinfunction "2_2") (pintype "passive"))
      (node (ref "C22") (pin "2") (pinfunction "2_2") (pintype "passive"))
      (node (ref "C23") (pin "2") (pinfunction "2_2") (pintype "passive"))
      (node (ref "C24") (pin "2") (pinfunction "2_2") (pintype "passive"))
      (node (ref "C25") (pin "2") (pinfunction "2_2") (pintype "passive"))
      (node (ref "C26") (pin "2") (pinfunction "2_2") (pintype "passive"))
      (node (ref "C27") (pin "2") (pinfunction "2_2") (pintype "passive"))
      (node (ref "C28") (pin "2") (pinfunction "2_2") (pintype "passive"))
      (node (ref "C29") (pin "2") (pinfunction "2_2") (pintype "passive"))
      (node (ref "C3") (pin "2") (pinfunction "2_2") (pintype "passive"))
      (node (ref "C30") (pin "2") (pinfunction "2_2") (pintype "passive"))
      (node (ref "C31") (pin "2") (pinfunction "2_2") (pintype "passive"))
      (node (ref "C32") (pin "2") (pinfunction "2_2") (pintype "passive"))
      (node (ref "C33") (pin "2") (pinfunction "2_2") (pintype "passive"))
      (node (ref "C34") (pin "2") (pinfunction "2_2") (pintype "passive"))
      (node (ref "C35") (pin "2") (pinfunction "2_2") (pintype "passive"))
      (node (ref "C36") (pin "2") (pinfunction "2_2") (pintype "passive"))
      (node (ref "C37") (pin "2") (pinfunction "2_2") (pintype "passive"))
      (node (ref "C38") (pin "2") (pinfunction "2_2") (pintype "passive"))
      (node (ref "C39") (pin "2") (pinfunction "2_2") (pintype "passive"))
      (node (ref "C4") (pin "2") (pinfunction "2_2") (pintype "passive"))
      (node (ref "C40") (pin "-") (pinfunction "-_-") (pintype "passive"))
      (node (ref "C5") (pin "2") (pinfunction "2_2") (pintype "passive"))
      (node (ref "C6") (pin "2") (pinfunction "2_2") (pintype "passive"))
      (node (ref "C7") (pin "2") (pinfunction "2_2") (pintype "passive"))
      (node (ref "C8") (pin "2") (pinfunction "2_2") (pintype "passive"))
      (node (ref "C9") (pin "2") (pinfunction "2_2") (pintype "passive"))
      (node (ref "D34L1") (pin "A") (pinfunction "1_A") (pintype "bidirectional"))
      (node (ref "D34L1") (pin "AA") (pinfunction "23_AA") (pintype "bidirectional"))
      (node (ref "D34L1") (pin "C") (pinfunction "3_C") (pintype "bidirectional"))
      (node (ref "D34L1") (pin "CC") (pinfunction "25_CC") (pintype "bidirectional"))
      (node (ref "D34L1") (pin "E") (pinfunction "5_E") (pintype "bidirectional"))
      (node (ref "D34L1") (pin "EE") (pinfunction "27_EE") (pintype "bidirectional"))
      (node (ref "D34L1") (pin "H") (pinfunction "7_H") (pintype "bidirectional"))
      (node (ref "D34L1") (pin "HH") (pinfunction "29_HH") (pintype "bidirectional"))
      (node (ref "D34L1") (pin "K") (pinfunction "9_K") (pintype "bidirectional"))
      (node (ref "D34L1") (pin "KK") (pinfunction "31_KK") (pintype "bidirectional"))
      (node (ref "D34L1") (pin "M") (pinfunction "11_M") (pintype "bidirectional"))
      (node (ref "D34L1") (pin "MM") (pinfunction "33_MM") (pintype "bidirectional"))
      (node (ref "D34L1") (pin "P") (pinfunction "13_P") (pintype "bidirectional"))
      (node (ref "D34L1") (pin "PP") (pinfunction "35_PP") (pintype "bidirectional"))
      (node (ref "D34L1") (pin "S") (pinfunction "15_S") (pintype "bidirectional"))
      (node (ref "D34L1") (pin "SS") (pinfunction "37_SS") (pintype "bidirectional"))
      (node (ref "D34L1") (pin "U") (pinfunction "17_U") (pintype "bidirectional"))
      (node (ref "D34L1") (pin "UU") (pinfunction "39_UU") (pintype "bidirectional"))
      (node (ref "D34L1") (pin "W") (pinfunction "19_W") (pintype "bidirectional"))
      (node (ref "D34L1") (pin "Y") (pinfunction "21_Y") (pintype "bidirectional"))
      (node (ref "D34L2") (pin "A") (pinfunction "1_A") (pintype "bidirectional"))
      (node (ref "D34L2") (pin "AA") (pinfunction "23_AA") (pintype "bidirectional"))
      (node (ref "D34L2") (pin "C") (pinfunction "3_C") (pintype "bidirectional"))
      (node (ref "D34L2") (pin "CC") (pinfunction "25_CC") (pintype "bidirectional"))
      (node (ref "D34L2") (pin "E") (pinfunction "5_E") (pintype "bidirectional"))
      (node (ref "D34L2") (pin "EE") (pinfunction "27_EE") (pintype "bidirectional"))
      (node (ref "D34L2") (pin "H") (pinfunction "7_H") (pintype "bidirectional"))
      (node (ref "D34L2") (pin "HH") (pinfunction "29_HH") (pintype "bidirectional"))
      (node (ref "D34L2") (pin "K") (pinfunction "9_K") (pintype "bidirectional"))
      (node (ref "D34L2") (pin "KK") (pinfunction "31_KK") (pintype "bidirectional"))
      (node (ref "D34L2") (pin "M") (pinfunction "11_M") (pintype "bidirectional"))
      (node (ref "D34L2") (pin "MM") (pinfunction "33_MM") (pintype "bidirectional"))
      (node (ref "D34L2") (pin "P") (pinfunction "13_P") (pintype "bidirectional"))
      (node (ref "D34L2") (pin "PP") (pinfunction "35_PP") (pintype "bidirectional"))
      (node (ref "D34L2") (pin "S") (pinfunction "15_S") (pintype "bidirectional"))
      (node (ref "D34L2") (pin "SS") (pinfunction "37_SS") (pintype "bidirectional"))
      (node (ref "D34L2") (pin "U") (pinfunction "17_U") (pintype "bidirectional"))
      (node (ref "D34L2") (pin "UU") (pinfunction "39_UU") (pintype "bidirectional"))
      (node (ref "D34L2") (pin "W") (pinfunction "19_W") (pintype "bidirectional"))
      (node (ref "D34L2") (pin "Y") (pinfunction "21_Y") (pintype "bidirectional"))
      (node (ref "D35L1") (pin "A") (pinfunction "1_A") (pintype "bidirectional"))
      (node (ref "D35L1") (pin "AA") (pinfunction "23_AA") (pintype "bidirectional"))
      (node (ref "D35L1") (pin "C") (pinfunction "3_C") (pintype "bidirectional"))
      (node (ref "D35L1") (pin "CC") (pinfunction "25_CC") (pintype "bidirectional"))
      (node (ref "D35L1") (pin "E") (pinfunction "5_E") (pintype "bidirectional"))
      (node (ref "D35L1") (pin "EE") (pinfunction "27_EE") (pintype "bidirectional"))
      (node (ref "D35L1") (pin "H") (pinfunction "7_H") (pintype "bidirectional"))
      (node (ref "D35L1") (pin "HH") (pinfunction "29_HH") (pintype "bidirectional"))
      (node (ref "D35L1") (pin "K") (pinfunction "9_K") (pintype "bidirectional"))
      (node (ref "D35L1") (pin "KK") (pinfunction "31_KK") (pintype "bidirectional"))
      (node (ref "D35L1") (pin "M") (pinfunction "11_M") (pintype "bidirectional"))
      (node (ref "D35L1") (pin "MM") (pinfunction "33_MM") (pintype "bidirectional"))
      (node (ref "D35L1") (pin "P") (pinfunction "13_P") (pintype "bidirectional"))
      (node (ref "D35L1") (pin "PP") (pinfunction "35_PP") (pintype "bidirectional"))
      (node (ref "D35L1") (pin "S") (pinfunction "15_S") (pintype "bidirectional"))
      (node (ref "D35L1") (pin "SS") (pinfunction "37_SS") (pintype "bidirectional"))
      (node (ref "D35L1") (pin "U") (pinfunction "17_U") (pintype "bidirectional"))
      (node (ref "D35L1") (pin "UU") (pinfunction "39_UU") (pintype "bidirectional"))
      (node (ref "D35L1") (pin "W") (pinfunction "19_W") (pintype "bidirectional"))
      (node (ref "D35L1") (pin "Y") (pinfunction "21_Y") (pintype "bidirectional"))
      (node (ref "D35L2") (pin "A") (pinfunction "1_A") (pintype "bidirectional"))
      (node (ref "D35L2") (pin "AA") (pinfunction "23_AA") (pintype "bidirectional"))
      (node (ref "D35L2") (pin "C") (pinfunction "3_C") (pintype "bidirectional"))
      (node (ref "D35L2") (pin "CC") (pinfunction "25_CC") (pintype "bidirectional"))
      (node (ref "D35L2") (pin "E") (pinfunction "5_E") (pintype "bidirectional"))
      (node (ref "D35L2") (pin "EE") (pinfunction "27_EE") (pintype "bidirectional"))
      (node (ref "D35L2") (pin "H") (pinfunction "7_H") (pintype "bidirectional"))
      (node (ref "D35L2") (pin "HH") (pinfunction "29_HH") (pintype "bidirectional"))
      (node (ref "D35L2") (pin "K") (pinfunction "9_K") (pintype "bidirectional"))
      (node (ref "D35L2") (pin "KK") (pinfunction "31_KK") (pintype "bidirectional"))
      (node (ref "D35L2") (pin "M") (pinfunction "11_M") (pintype "bidirectional"))
      (node (ref "D35L2") (pin "MM") (pinfunction "33_MM") (pintype "bidirectional"))
      (node (ref "D35L2") (pin "P") (pinfunction "13_P") (pintype "bidirectional"))
      (node (ref "D35L2") (pin "PP") (pinfunction "35_PP") (pintype "bidirectional"))
      (node (ref "D35L2") (pin "S") (pinfunction "15_S") (pintype "bidirectional"))
      (node (ref "D35L2") (pin "SS") (pinfunction "37_SS") (pintype "bidirectional"))
      (node (ref "D35L2") (pin "U") (pinfunction "17_U") (pintype "bidirectional"))
      (node (ref "D35L2") (pin "UU") (pinfunction "39_UU") (pintype "bidirectional"))
      (node (ref "D35L2") (pin "W") (pinfunction "19_W") (pintype "bidirectional"))
      (node (ref "D35L2") (pin "Y") (pinfunction "21_Y") (pintype "bidirectional"))
      (node (ref "D36L1") (pin "A") (pinfunction "1_A") (pintype "bidirectional"))
      (node (ref "D36L1") (pin "AA") (pinfunction "23_AA") (pintype "bidirectional"))
      (node (ref "D36L1") (pin "C") (pinfunction "3_C") (pintype "bidirectional"))
      (node (ref "D36L1") (pin "CC") (pinfunction "25_CC") (pintype "bidirectional"))
      (node (ref "D36L1") (pin "E") (pinfunction "5_E") (pintype "bidirectional"))
      (node (ref "D36L1") (pin "EE") (pinfunction "27_EE") (pintype "bidirectional"))
      (node (ref "D36L1") (pin "H") (pinfunction "7_H") (pintype "bidirectional"))
      (node (ref "D36L1") (pin "HH") (pinfunction "29_HH") (pintype "bidirectional"))
      (node (ref "D36L1") (pin "K") (pinfunction "9_K") (pintype "bidirectional"))
      (node (ref "D36L1") (pin "KK") (pinfunction "31_KK") (pintype "bidirectional"))
      (node (ref "D36L1") (pin "M") (pinfunction "11_M") (pintype "bidirectional"))
      (node (ref "D36L1") (pin "MM") (pinfunction "33_MM") (pintype "bidirectional"))
      (node (ref "D36L1") (pin "P") (pinfunction "13_P") (pintype "bidirectional"))
      (node (ref "D36L1") (pin "PP") (pinfunction "35_PP") (pintype "bidirectional"))
      (node (ref "D36L1") (pin "S") (pinfunction "15_S") (pintype "bidirectional"))
      (node (ref "D36L1") (pin "SS") (pinfunction "37_SS") (pintype "bidirectional"))
      (node (ref "D36L1") (pin "U") (pinfunction "17_U") (pintype "bidirectional"))
      (node (ref "D36L1") (pin "UU") (pinfunction "39_UU") (pintype "bidirectional"))
      (node (ref "D36L1") (pin "W") (pinfunction "19_W") (pintype "bidirectional"))
      (node (ref "D36L1") (pin "Y") (pinfunction "21_Y") (pintype "bidirectional"))
      (node (ref "D36L2") (pin "A") (pinfunction "1_A") (pintype "bidirectional"))
      (node (ref "D36L2") (pin "AA") (pinfunction "23_AA") (pintype "bidirectional"))
      (node (ref "D36L2") (pin "C") (pinfunction "3_C") (pintype "bidirectional"))
      (node (ref "D36L2") (pin "CC") (pinfunction "25_CC") (pintype "bidirectional"))
      (node (ref "D36L2") (pin "E") (pinfunction "5_E") (pintype "bidirectional"))
      (node (ref "D36L2") (pin "EE") (pinfunction "27_EE") (pintype "bidirectional"))
      (node (ref "D36L2") (pin "H") (pinfunction "7_H") (pintype "bidirectional"))
      (node (ref "D36L2") (pin "HH") (pinfunction "29_HH") (pintype "bidirectional"))
      (node (ref "D36L2") (pin "K") (pinfunction "9_K") (pintype "bidirectional"))
      (node (ref "D36L2") (pin "KK") (pinfunction "31_KK") (pintype "bidirectional"))
      (node (ref "D36L2") (pin "M") (pinfunction "11_M") (pintype "bidirectional"))
      (node (ref "D36L2") (pin "MM") (pinfunction "33_MM") (pintype "bidirectional"))
      (node (ref "D36L2") (pin "P") (pinfunction "13_P") (pintype "bidirectional"))
      (node (ref "D36L2") (pin "PP") (pinfunction "35_PP") (pintype "bidirectional"))
      (node (ref "D36L2") (pin "S") (pinfunction "15_S") (pintype "bidirectional"))
      (node (ref "D36L2") (pin "SS") (pinfunction "37_SS") (pintype "bidirectional"))
      (node (ref "D36L2") (pin "U") (pinfunction "17_U") (pintype "bidirectional"))
      (node (ref "D36L2") (pin "UU") (pinfunction "39_UU") (pintype "bidirectional"))
      (node (ref "D36L2") (pin "W") (pinfunction "19_W") (pintype "bidirectional"))
      (node (ref "D36L2") (pin "Y") (pinfunction "21_Y") (pintype "bidirectional"))
      (node (ref "DRIVE") (pin "A") (pinfunction "1_A") (pintype "bidirectional"))
      (node (ref "DRIVE") (pin "AA") (pinfunction "23_AA") (pintype "bidirectional"))
      (node (ref "DRIVE") (pin "B") (pinfunction "2_B") (pintype "bidirectional"))
      (node (ref "DRIVE") (pin "C") (pinfunction "3_C") (pintype "bidirectional"))
      (node (ref "DRIVE") (pin "CC") (pinfunction "25_CC") (pintype "bidirectional"))
      (node (ref "DRIVE") (pin "DD") (pinfunction "26_DD") (pintype "bidirectional"))
      (node (ref "DRIVE") (pin "E") (pinfunction "5_E") (pintype "bidirectional"))
      (node (ref "DRIVE") (pin "EE") (pinfunction "27_EE") (pintype "bidirectional"))
      (node (ref "DRIVE") (pin "F") (pinfunction "6_F") (pintype "bidirectional"))
      (node (ref "DRIVE") (pin "H") (pinfunction "7_H") (pintype "bidirectional"))
      (node (ref "DRIVE") (pin "HH") (pinfunction "29_HH") (pintype "bidirectional"))
      (node (ref "DRIVE") (pin "JJ") (pinfunction "30_JJ") (pintype "bidirectional"))
      (node (ref "DRIVE") (pin "K") (pinfunction "9_K") (pintype "bidirectional"))
      (node (ref "DRIVE") (pin "KK") (pinfunction "31_KK") (pintype "bidirectional"))
      (node (ref "DRIVE") (pin "L") (pinfunction "10_L") (pintype "bidirectional"))
      (node (ref "DRIVE") (pin "M") (pinfunction "11_M") (pintype "bidirectional"))
      (node (ref "DRIVE") (pin "MM") (pinfunction "33_MM") (pintype "bidirectional"))
      (node (ref "DRIVE") (pin "NN") (pinfunction "34_NN") (pintype "bidirectional"))
      (node (ref "DRIVE") (pin "P") (pinfunction "13_P") (pintype "bidirectional"))
      (node (ref "DRIVE") (pin "PP") (pinfunction "35_PP") (pintype "bidirectional"))
      (node (ref "DRIVE") (pin "R") (pinfunction "14_R") (pintype "bidirectional"))
      (node (ref "DRIVE") (pin "S") (pinfunction "15_S") (pintype "bidirectional"))
      (node (ref "DRIVE") (pin "SS") (pinfunction "37_SS") (pintype "bidirectional"))
      (node (ref "DRIVE") (pin "TT") (pinfunction "38_TT") (pintype "bidirectional"))
      (node (ref "DRIVE") (pin "U") (pinfunction "17_U") (pintype "bidirectional"))
      (node (ref "DRIVE") (pin "UU") (pinfunction "39_UU") (pintype "bidirectional"))
      (node (ref "DRIVE") (pin "V") (pinfunction "18_V") (pintype "bidirectional"))
      (node (ref "DRIVE") (pin "VV") (pinfunction "40_VV") (pintype "bidirectional"))
      (node (ref "DRIVE") (pin "W") (pinfunction "19_W") (pintype "bidirectional"))
      (node (ref "DRIVE") (pin "Y") (pinfunction "21_Y") (pintype "bidirectional"))
      (node (ref "DRIVE") (pin "Z") (pinfunction "22_Z") (pintype "bidirectional"))
      (node (ref "E11") (pin "5") (pinfunction "G2B_5") (pintype "input"))
      (node (ref "E12") (pin "5") (pinfunction "G2B_5") (pintype "input"))
      (node (ref "E13") (pin "5") (pinfunction "G2B_5") (pintype "input"))
      (node (ref "E2") (pin "2") (pinfunction "D_2") (pintype "input"))
      (node (ref "E4") (pin "6") (pinfunction "D_6") (pintype "input"))
      (node (ref "LASTDEV") (pin "1") (pinfunction "1_1") (pintype "passive"))
      (node (ref "R10") (pin "1") (pinfunction "1_1") (pintype "passive"))
      (node (ref "R11") (pin "1") (pinfunction "1_1") (pintype "passive"))
      (node (ref "R12") (pin "1") (pinfunction "1_1") (pintype "passive"))
      (node (ref "R13") (pin "1") (pinfunction "1_1") (pintype "passive"))
      (node (ref "R14") (pin "1") (pinfunction "1_1") (pintype "passive"))
      (node (ref "R15") (pin "1") (pinfunction "1_1") (pintype "passive"))
      (node (ref "R16") (pin "1") (pinfunction "1_1") (pintype "passive"))
      (node (ref "R17") (pin "1") (pinfunction "1_1") (pintype "passive"))
      (node (ref "SL1") (pin "2") (pinfunction "S_2") (pintype "passive"))
      (node (ref "SL1") (pin "3") (pinfunction "S_3") (pintype "passive"))
    )
    (net (code "40") (name "INIT") (class "Default")
      (node (ref "E1") (pin "8") (pinfunction "O_8") (pintype "output"))
      (node (ref "E15") (pin "4") (pinfunction "I0_4") (pintype "input"))
      (node (ref "E15") (pin "5") (pinfunction "I1_5") (pintype "input"))
      (node (ref "E18") (pin "12") (pinfunction "I1_12") (pintype "input"))
      (node (ref "IC8") (pin "6") (pinfunction "I0_6") (pintype "input"))
      (node (ref "IC8") (pin "7") (pinfunction "I1_7") (pintype "input"))
    )
    (net (code "41") (name "MAINT") (class "Default")
      (node (ref "E16") (pin "9") (pinfunction "Q_9") (pintype "output"))
      (node (ref "E32") (pin "9") (pinfunction "I0_9") (pintype "input"))
      (node (ref "E35") (pin "3") (pinfunction "I1_3") (pintype "input"))
      (node (ref "E35") (pin "6") (pinfunction "I1_6") (pintype "input"))
      (node (ref "E35") (pin "9") (pinfunction "I1_9") (pintype "input"))
      (node (ref "E36") (pin "2") (pinfunction "I0_2") (pintype "input"))
      (node (ref "E36") (pin "6") (pinfunction "I1_6") (pintype "input"))
      (node (ref "E36") (pin "9") (pinfunction "I1_9") (pintype "input"))
    )
    (net (code "42") (name "MSB8") (class "Default")
      (node (ref "E21") (pin "12") (pinfunction "QD_12") (pintype "output"))
      (node (ref "E23") (pin "2") (pinfunction "J_2") (pintype "input"))
      (node (ref "E23") (pin "3") (pinfunction "K_3") (pintype "input"))
      (node (ref "E8") (pin "5") (pinfunction "I2_5") (pintype "input"))
      (node (ref "IC1") (pin "6") (pinfunction "I0_6") (pintype "input"))
    )
    (net (code "43") (name "MSB12") (class "Default")
      (node (ref "E23") (pin "12") (pinfunction "QD_12") (pintype "output"))
      (node (ref "E8") (pin "2") (pinfunction "I1_2") (pintype "input"))
      (node (ref "IC6") (pin "1") (pinfunction "I0_1") (pintype "input"))
    )
    (net (code "44") (name "Net-(70-P)") (class "Default")
      (node (ref "70") (pin "1") (pinfunction "P_1") (pintype "passive"))
      (node (ref "E14") (pin "15") (pinfunction "Y0_15") (pintype "output"))
    )
    (net (code "45") (name "Net-(71-P)") (class "Default")
      (node (ref "71") (pin "1") (pinfunction "P_1") (pintype "passive"))
      (node (ref "E14") (pin "14") (pinfunction "Y1_14") (pintype "output"))
    )
    (net (code "46") (name "Net-(72-P)") (class "Default")
      (node (ref "72") (pin "1") (pinfunction "P_1") (pintype "passive"))
      (node (ref "E14") (pin "13") (pinfunction "Y2_13") (pintype "output"))
    )
    (net (code "47") (name "Net-(73-P)") (class "Default")
      (node (ref "73") (pin "1") (pinfunction "P_1") (pintype "passive"))
      (node (ref "E14") (pin "12") (pinfunction "Y3_12") (pintype "output"))
    )
    (net (code "48") (name "Net-(74-P)") (class "Default")
      (node (ref "74") (pin "1") (pinfunction "P_1") (pintype "passive"))
      (node (ref "E14") (pin "11") (pinfunction "Y4_11") (pintype "output"))
    )
    (net (code "49") (name "Net-(75-P)") (class "Default")
      (node (ref "75") (pin "1") (pinfunction "P_1") (pintype "passive"))
      (node (ref "E14") (pin "10") (pinfunction "Y5_10") (pintype "output"))
    )
    (net (code "50") (name "Net-(76-P)") (class "Default")
      (node (ref "76") (pin "1") (pinfunction "P_1") (pintype "passive"))
      (node (ref "E14") (pin "9") (pinfunction "Y6_9") (pintype "output"))
    )
    (net (code "51") (name "Net-(77-P)") (class "Default")
      (node (ref "77") (pin "1") (pinfunction "P_1") (pintype "passive"))
      (node (ref "E14") (pin "7") (pinfunction "Y7_7") (pintype "output"))
    )
    (net (code "52") (name "Net-(E1B-O)") (class "Default")
      (node (ref "E1") (pin "10") (pinfunction "I1_10") (pintype "input"))
      (node (ref "E1") (pin "6") (pinfunction "O_6") (pintype "output"))
      (node (ref "E1") (pin "9") (pinfunction "I0_9") (pintype "input"))
      (node (ref "E2") (pin "1") (pinfunction "CLR_1") (pintype "input"))
    )
    (net (code "53") (name "Net-(E1C-I2)") (class "Default")
      (node (ref "E1") (pin "11") (pinfunction "I2_11") (pintype "input"))
      (node (ref "E2") (pin "6") (pinfunction "~{Q}_6") (pintype "output"))
    )
    (net (code "54") (name "Net-(E4A-A)") (class "Default")
      (node (ref "E4") (pin "10") (pinfunction "ENT_10") (pintype "input"))
      (node (ref "E4") (pin "3") (pinfunction "A_3") (pintype "input"))
      (node (ref "E4") (pin "4") (pinfunction "B_4") (pintype "input"))
      (node (ref "E4") (pin "7") (pinfunction "ENP_7") (pintype "input"))
      (node (ref "R19") (pin "2") (pinfunction "2_2") (pintype "passive"))
    )
    (net (code "55") (name "Net-(E4A-C)") (class "Default")
      (node (ref "E4") (pin "5") (pinfunction "C_5") (pintype "input"))
      (node (ref "E5") (pin "3") (pinfunction "O_3") (pintype "output"))
    )
    (net (code "56") (name "Net-(E5A-I0)") (class "Default")
      (node (ref "E5") (pin "1") (pinfunction "I0_1") (pintype "input"))
      (node (ref "E5") (pin "11") (pinfunction "O_11") (pintype "output"))
    )
    (net (code "57") (name "Net-(E8A-O)") (class "Default")
      (node (ref "E8") (pin "11") (pinfunction "I2_11") (pintype "input"))
      (node (ref "E8") (pin "12") (pinfunction "O_12") (pintype "output"))
    )
    (net (code "58") (name "Net-(E8B-O)") (class "Default")
      (node (ref "E8") (pin "6") (pinfunction "O_6") (pintype "output"))
      (node (ref "E8") (pin "9") (pinfunction "I0_9") (pintype "input"))
    )
    (net (code "59") (name "Net-(E10A-I0)") (class "Default")
      (node (ref "E10") (pin "1") (pinfunction "I0_1") (pintype "input"))
      (node (ref "E10") (pin "6") (pinfunction "O_6") (pintype "output"))
    )
    (net (code "60") (name "Net-(E10A-O)") (class "Default")
      (node (ref "E10") (pin "10") (pinfunction "I1_10") (pintype "input"))
      (node (ref "E10") (pin "11") (pinfunction "I2_11") (pintype "input"))
      (node (ref "E10") (pin "12") (pinfunction "O_12") (pintype "output"))
    )
    (net (code "61") (name "Net-(E10C-O)") (class "Default")
      (node (ref "E10") (pin "8") (pinfunction "O_8") (pintype "output"))
      (node (ref "IC7") (pin "1") (pinfunction "I0_1") (pintype "input"))
      (node (ref "IC7") (pin "2") (pinfunction "I1_2") (pintype "input"))
    )
    (net (code "62") (name "Net-(E14A-G2A)") (class "Default")
      (node (ref "E1") (pin "12") (pinfunction "O_12") (pintype "output"))
      (node (ref "E14") (pin "4") (pinfunction "G2A_4") (pintype "input"))
      (node (ref "E14") (pin "5") (pinfunction "G2B_5") (pintype "input"))
    )
    (net (code "63") (name "Net-(E15A-O)") (class "Default")
      (node (ref "E15") (pin "3") (pinfunction "O_3") (pintype "output"))
      (node (ref "E8") (pin "13") (pinfunction "I2_13") (pintype "input"))
      (node (ref "E8") (pin "3") (pinfunction "I0_3") (pintype "input"))
    )
    (net (code "64") (name "Net-(E15C-I0)") (class "Default")
      (node (ref "E15") (pin "9") (pinfunction "I0_9") (pintype "input"))
      (node (ref "E20") (pin "11") (pinfunction "O_11") (pintype "output"))
      (node (ref "E24") (pin "10") (pinfunction "I1_10") (pintype "input"))
    )
    (net (code "65") (name "Net-(E15C-O)") (class "Default")
      (node (ref "E15") (pin "8") (pinfunction "O_8") (pintype "output"))
      (node (ref "E24") (pin "12") (pinfunction "I0_12") (pintype "input"))
    )
    (net (code "66") (name "Net-(E15D-O)") (class "Default")
      (node (ref "E15") (pin "11") (pinfunction "O_11") (pintype "output"))
      (node (ref "E8") (pin "10") (pinfunction "I1_10") (pintype "input"))
    )
    (net (code "67") (name "Net-(E17A-CLK)") (class "Default")
      (node (ref "E17") (pin "1") (pinfunction "CLK_1") (pintype "input"))
      (node (ref "IC11") (pin "6") (pinfunction "O_6") (pintype "output"))
    )
    (net (code "68") (name "Net-(E17A-~{Q})") (class "Default")
      (node (ref "E17") (pin "14") (pinfunction "~{Q}_14") (pintype "output"))
      (node (ref "E18") (pin "9") (pinfunction "I1_9") (pintype "input"))
    )
    (net (code "69") (name "Net-(E17B-CLR)") (class "Default")
      (node (ref "E17") (pin "8") (pinfunction "CLR_8") (pintype "input"))
      (node (ref "E18") (pin "13") (pinfunction "O_13") (pintype "output"))
    )
    (net (code "70") (name "Net-(E17B-J)") (class "Default")
      (node (ref "E17") (pin "12") (pinfunction "K_12") (pintype "input"))
      (node (ref "E17") (pin "9") (pinfunction "J_9") (pintype "input"))
      (node (ref "E8") (pin "8") (pinfunction "O_8") (pintype "output"))
      (node (ref "IC7") (pin "7") (pinfunction "I1_7") (pintype "input"))
    )
    (net (code "71") (name "Net-(E18A-I1)") (class "Default")
      (node (ref "E18") (pin "3") (pinfunction "I1_3") (pintype "input"))
      (node (ref "E19") (pin "14") (pinfunction "~{Q}_14") (pintype "output"))
    )
    (net (code "72") (name "Net-(E18B-I1)") (class "Default")
      (node (ref "E18") (pin "6") (pinfunction "I1_6") (pintype "input"))
      (node (ref "E19") (pin "10") (pinfunction "~{Q}_10") (pintype "output"))
    )
    (net (code "73") (name "Net-(E19A-CLK)") (class "Default")
      (node (ref "E19") (pin "1") (pinfunction "CLK_1") (pintype "input"))
      (node (ref "IC11") (pin "2") (pinfunction "O_2") (pintype "output"))
    )
    (net (code "74") (name "Net-(E19B-CLK)") (class "Default")
      (node (ref "E19") (pin "6") (pinfunction "CLK_6") (pintype "input"))
      (node (ref "IC11") (pin "4") (pinfunction "O_4") (pintype "output"))
    )
    (net (code "75") (name "Net-(E20A-I1)") (class "Default")
      (node (ref "E20") (pin "2") (pinfunction "I1_2") (pintype "input"))
      (node (ref "E20") (pin "6") (pinfunction "O_6") (pintype "output"))
    )
    (net (code "76") (name "Net-(E20A-O)") (class "Default")
      (node (ref "E20") (pin "3") (pinfunction "O_3") (pintype "output"))
      (node (ref "IC10") (pin "1") (pinfunction "I0_1") (pintype "input"))
      (node (ref "IC10") (pin "2") (pinfunction "I1_2") (pintype "input"))
    )
    (net (code "77") (name "Net-(E21A-J)") (class "Default")
      (node (ref "E21") (pin "2") (pinfunction "J_2") (pintype "input"))
      (node (ref "E21") (pin "3") (pinfunction "K_3") (pintype "input"))
      (node (ref "E22") (pin "12") (pinfunction "QD_12") (pintype "output"))
      (node (ref "IC4") (pin "6") (pinfunction "I0_6") (pintype "input"))
    )
    (net (code "78") (name "Net-(E21A-QA)") (class "Default")
      (node (ref "E21") (pin "15") (pinfunction "QA_15") (pintype "output"))
      (node (ref "IC3") (pin "6") (pinfunction "I0_6") (pintype "input"))
    )
    (net (code "79") (name "Net-(E21A-QB)") (class "Default")
      (node (ref "E21") (pin "14") (pinfunction "QB_14") (pintype "output"))
      (node (ref "IC3") (pin "1") (pinfunction "I0_1") (pintype "input"))
    )
    (net (code "80") (name "Net-(E21A-QC)") (class "Default")
      (node (ref "E21") (pin "13") (pinfunction "QC_13") (pintype "output"))
      (node (ref "IC4") (pin "1") (pinfunction "I0_1") (pintype "input"))
    )
    (net (code "81") (name "Net-(E22A-QA)") (class "Default")
      (node (ref "E22") (pin "15") (pinfunction "QA_15") (pintype "output"))
      (node (ref "IC2") (pin "1") (pinfunction "I0_1") (pintype "input"))
    )
    (net (code "82") (name "Net-(E22A-QB)") (class "Default")
      (node (ref "E22") (pin "14") (pinfunction "QB_14") (pintype "output"))
      (node (ref "IC5") (pin "6") (pinfunction "I0_6") (pintype "input"))
    )
    (net (code "83") (name "Net-(E22A-QC)") (class "Default")
      (node (ref "E22") (pin "13") (pinfunction "QC_13") (pintype "output"))
      (node (ref "IC5") (pin "1") (pinfunction "I0_1") (pintype "input"))
    )
    (net (code "84") (name "Net-(E23A-QA)") (class "Default")
      (node (ref "E23") (pin "15") (pinfunction "QA_15") (pintype "output"))
      (node (ref "IC2") (pin "6") (pinfunction "I0_6") (pintype "input"))
    )
    (net (code "85") (name "Net-(E23A-QB)") (class "Default")
      (node (ref "E23") (pin "14") (pinfunction "QB_14") (pintype "output"))
      (node (ref "IC1") (pin "1") (pinfunction "I0_1") (pintype "input"))
    )
    (net (code "86") (name "Net-(E23A-QC)") (class "Default")
      (node (ref "E23") (pin "13") (pinfunction "QC_13") (pintype "output"))
      (node (ref "IC6") (pin "6") (pinfunction "I0_6") (pintype "input"))
    )
    (net (code "87") (name "Net-(E24A-I1)") (class "Default")
      (node (ref "E24") (pin "2") (pinfunction "I1_2") (pintype "input"))
      (node (ref "E35") (pin "13") (pinfunction "O_13") (pintype "output"))
      (node (ref "IC1") (pin "7") (pinfunction "I1_7") (pintype "input"))
      (node (ref "IC2") (pin "2") (pinfunction "I1_2") (pintype "input"))
      (node (ref "IC3") (pin "2") (pinfunction "I1_2") (pintype "input"))
      (node (ref "IC3") (pin "7") (pinfunction "I1_7") (pintype "input"))
      (node (ref "IC4") (pin "2") (pinfunction "I1_2") (pintype "input"))
      (node (ref "IC4") (pin "7") (pinfunction "I1_7") (pintype "input"))
      (node (ref "IC5") (pin "2") (pinfunction "I1_2") (pintype "input"))
      (node (ref "IC5") (pin "7") (pinfunction "I1_7") (pintype "input"))
    )
    (net (code "88") (name "Net-(E24A-O)") (class "Default")
      (node (ref "E24") (pin "3") (pinfunction "O_3") (pintype "output"))
      (node (ref "IC1") (pin "2") (pinfunction "I1_2") (pintype "input"))
      (node (ref "IC2") (pin "7") (pinfunction "I1_7") (pintype "input"))
      (node (ref "IC6") (pin "2") (pinfunction "I1_2") (pintype "input"))
      (node (ref "IC6") (pin "7") (pinfunction "I1_7") (pintype "input"))
    )
    (net (code "89") (name "Net-(E24B-O)") (class "Default")
      (node (ref "E24") (pin "6") (pinfunction "O_6") (pintype "output"))
      (node (ref "E32") (pin "1") (pinfunction "I0_1") (pintype "input"))
    )
    (net (code "90") (name "Net-(E24C-O)") (class "Default")
      (node (ref "E24") (pin "8") (pinfunction "O_8") (pintype "output"))
      (node (ref "E30") (pin "13") (pinfunction "CLR_13") (pintype "input"))
    )
    (net (code "91") (name "Net-(E25C-O)") (class "Default")
      (node (ref "E25") (pin "6") (pinfunction "O_6") (pintype "output"))
      (node (ref "E31") (pin "1") (pinfunction "I0_1") (pintype "input"))
      (node (ref "E31") (pin "2") (pinfunction "I1_2") (pintype "input"))
    )
    (net (code "92") (name "Net-(E25D-O)") (class "Default")
      (node (ref "E25") (pin "8") (pinfunction "O_8") (pintype "output"))
      (node (ref "E31") (pin "13") (pinfunction "I3_13") (pintype "input"))
    )
    (net (code "93") (name "Net-(E25E-O)") (class "Default")
      (node (ref "E25") (pin "10") (pinfunction "O_10") (pintype "output"))
      (node (ref "E26") (pin "12") (pinfunction "I0_12") (pintype "input"))
      (node (ref "E26") (pin "13") (pinfunction "I1_13") (pintype "input"))
    )
    (net (code "94") (name "Net-(E25F-O)") (class "Default")
      (node (ref "E25") (pin "12") (pinfunction "O_12") (pintype "output"))
      (node (ref "E36") (pin "11") (pinfunction "I0_11") (pintype "input"))
      (node (ref "E36") (pin "12") (pinfunction "I1_12") (pintype "input"))
    )
    (net (code "95") (name "Net-(E26A-O)") (class "Default")
      (node (ref "E26") (pin "3") (pinfunction "O_3") (pintype "output"))
      (node (ref "IC11") (pin "1") (pinfunction "I_1") (pintype "input"))
    )
    (net (code "96") (name "Net-(E26B-O)") (class "Default")
      (node (ref "E26") (pin "6") (pinfunction "O_6") (pintype "output"))
      (node (ref "IC11") (pin "3") (pinfunction "I_3") (pintype "input"))
    )
    (net (code "97") (name "Net-(E26C-O)") (class "Default")
      (node (ref "E26") (pin "8") (pinfunction "O_8") (pintype "output"))
      (node (ref "IC11") (pin "5") (pinfunction "I_5") (pintype "input"))
    )
    (net (code "98") (name "Net-(E30A-Q)") (class "Default")
      (node (ref "E30") (pin "5") (pinfunction "Q_5") (pintype "output"))
      (node (ref "IC10") (pin "7") (pinfunction "I1_7") (pintype "input"))
    )
    (net (code "99") (name "Net-(E30B-CLK)") (class "Default")
      (node (ref "E30") (pin "11") (pinfunction "CLK_11") (pintype "input"))
      (node (ref "IC9") (pin "3") (pinfunction "O_3") (pintype "open_collector"))
      (node (ref "R18") (pin "1") (pinfunction "1_1") (pintype "passive"))
    )
    (net (code "100") (name "Net-(E31A-O)") (class "Default")
      (node (ref "E31") (pin "6") (pinfunction "O_6") (pintype "output"))
      (node (ref "IC9") (pin "1") (pinfunction "I0_1") (pintype "input"))
    )
    (net (code "101") (name "Net-(E31B-O)") (class "Default")
      (node (ref "E31") (pin "8") (pinfunction "O_8") (pintype "output"))
      (node (ref "IC9") (pin "2") (pinfunction "I1_2") (pintype "input"))
    )
    (net (code "102") (name "Net-(E32A-O)") (class "Default")
      (node (ref "E32") (pin "12") (pinfunction "O_12") (pintype "output"))
      (node (ref "E32") (pin "4") (pinfunction "I1_4") (pintype "input"))
      (node (ref "E32") (pin "5") (pinfunction "I2_5") (pintype "input"))
    )
    (net (code "103") (name "Net-(E32C-O)") (class "Default")
      (node (ref "E32") (pin "8") (pinfunction "O_8") (pintype "output"))
      (node (ref "E35") (pin "11") (pinfunction "I0_11") (pintype "input"))
    )
    (net (code "104") (name "Net-(PAD10-P)") (class "Default")
      (node (ref "E38") (pin "1") (pinfunction "1_1") (pintype "passive"))
      (node (ref "PAD10") (pin "1") (pinfunction "P_1") (pintype "passive"))
    )
    (net (code "105") (name "Net-(PAD11-P)") (class "Default")
      (node (ref "E38") (pin "2") (pinfunction "2_2") (pintype "passive"))
      (node (ref "PAD11") (pin "1") (pinfunction "P_1") (pintype "passive"))
    )
    (net (code "106") (name "Net-(PAD12-P)") (class "Default")
      (node (ref "E38") (pin "3") (pinfunction "3_3") (pintype "passive"))
      (node (ref "PAD12") (pin "1") (pinfunction "P_1") (pintype "passive"))
    )
    (net (code "107") (name "Net-(PAD13-P)") (class "Default")
      (node (ref "E38") (pin "4") (pinfunction "4_4") (pintype "passive"))
      (node (ref "PAD13") (pin "1") (pinfunction "P_1") (pintype "passive"))
    )
    (net (code "108") (name "Net-(PAD14-P)") (class "Default")
      (node (ref "E38") (pin "5") (pinfunction "5_5") (pintype "passive"))
      (node (ref "PAD14") (pin "1") (pinfunction "P_1") (pintype "passive"))
    )
    (net (code "109") (name "Net-(PAD15-P)") (class "Default")
      (node (ref "E38") (pin "6") (pinfunction "6_6") (pintype "passive"))
      (node (ref "PAD15") (pin "1") (pinfunction "P_1") (pintype "passive"))
    )
    (net (code "110") (name "Net-(PAD16-P)") (class "Default")
      (node (ref "E38") (pin "7") (pinfunction "7_7") (pintype "passive"))
      (node (ref "PAD16") (pin "1") (pinfunction "P_1") (pintype "passive"))
    )
    (net (code "111") (name "Net-(PAD17-P)") (class "Default")
      (node (ref "E38") (pin "8") (pinfunction "8_8") (pintype "passive"))
      (node (ref "PAD17") (pin "1") (pinfunction "P_1") (pintype "passive"))
    )
    (net (code "112") (name "Net-(PAD18-P)") (class "Default")
      (node (ref "E40") (pin "1") (pinfunction "1_1") (pintype "passive"))
      (node (ref "PAD18") (pin "1") (pinfunction "P_1") (pintype "passive"))
    )
    (net (code "113") (name "Net-(PAD19-P)") (class "Default")
      (node (ref "E40") (pin "2") (pinfunction "2_2") (pintype "passive"))
      (node (ref "PAD19") (pin "1") (pinfunction "P_1") (pintype "passive"))
    )
    (net (code "114") (name "Net-(PAD20-P)") (class "Default")
      (node (ref "E38") (pin "16") (pinfunction "16_16") (pintype "passive"))
      (node (ref "PAD20") (pin "1") (pinfunction "P_1") (pintype "passive"))
    )
    (net (code "115") (name "Net-(PAD21-P)") (class "Default")
      (node (ref "E38") (pin "15") (pinfunction "15_15") (pintype "passive"))
      (node (ref "PAD21") (pin "1") (pinfunction "P_1") (pintype "passive"))
    )
    (net (code "116") (name "Net-(PAD22-P)") (class "Default")
      (node (ref "E38") (pin "14") (pinfunction "14_14") (pintype "passive"))
      (node (ref "PAD22") (pin "1") (pinfunction "P_1") (pintype "passive"))
    )
    (net (code "117") (name "Net-(PAD23-P)") (class "Default")
      (node (ref "E38") (pin "13") (pinfunction "13_13") (pintype "passive"))
      (node (ref "PAD23") (pin "1") (pinfunction "P_1") (pintype "passive"))
    )
    (net (code "118") (name "Net-(PAD24-P)") (class "Default")
      (node (ref "E38") (pin "12") (pinfunction "12_12") (pintype "passive"))
      (node (ref "PAD24") (pin "1") (pinfunction "P_1") (pintype "passive"))
    )
    (net (code "119") (name "Net-(PAD25-P)") (class "Default")
      (node (ref "E38") (pin "11") (pinfunction "11_11") (pintype "passive"))
      (node (ref "PAD25") (pin "1") (pinfunction "P_1") (pintype "passive"))
    )
    (net (code "120") (name "Net-(PAD26-P)") (class "Default")
      (node (ref "E38") (pin "10") (pinfunction "10_10") (pintype "passive"))
      (node (ref "PAD26") (pin "1") (pinfunction "P_1") (pintype "passive"))
    )
    (net (code "121") (name "Net-(PAD27-P)") (class "Default")
      (node (ref "E38") (pin "9") (pinfunction "9_9") (pintype "passive"))
      (node (ref "PAD27") (pin "1") (pinfunction "P_1") (pintype "passive"))
    )
    (net (code "122") (name "Net-(PAD28-P)") (class "Default")
      (node (ref "E40") (pin "3") (pinfunction "3_3") (pintype "passive"))
      (node (ref "PAD28") (pin "1") (pinfunction "P_1") (pintype "passive"))
    )
    (net (code "123") (name "Net-(PAD29-P)") (class "Default")
      (node (ref "E40") (pin "4") (pinfunction "4_4") (pintype "passive"))
      (node (ref "PAD29") (pin "1") (pinfunction "P_1") (pintype "passive"))
    )
    (net (code "124") (name "Net-(PAD30-P)") (class "Default")
      (node (ref "E40") (pin "5") (pinfunction "5_5") (pintype "passive"))
      (node (ref "PAD30") (pin "1") (pinfunction "P_1") (pintype "passive"))
    )
    (net (code "125") (name "Net-(PAD31-P)") (class "Default")
      (node (ref "E40") (pin "6") (pinfunction "6_6") (pintype "passive"))
      (node (ref "PAD31") (pin "1") (pinfunction "P_1") (pintype "passive"))
    )
    (net (code "126") (name "Net-(PAD32-P)") (class "Default")
      (node (ref "E40") (pin "7") (pinfunction "7_7") (pintype "passive"))
      (node (ref "PAD32") (pin "1") (pinfunction "P_1") (pintype "passive"))
    )
    (net (code "127") (name "Net-(PAD33-P)") (class "Default")
      (node (ref "E40") (pin "8") (pinfunction "8_8") (pintype "passive"))
      (node (ref "PAD33") (pin "1") (pinfunction "P_1") (pintype "passive"))
    )
    (net (code "128") (name "Net-(PAD34-P)") (class "Default")
      (node (ref "E40") (pin "16") (pinfunction "16_16") (pintype "passive"))
      (node (ref "PAD34") (pin "1") (pinfunction "P_1") (pintype "passive"))
    )
    (net (code "129") (name "Net-(PAD35-P)") (class "Default")
      (node (ref "E40") (pin "15") (pinfunction "15_15") (pintype "passive"))
      (node (ref "PAD35") (pin "1") (pinfunction "P_1") (pintype "passive"))
    )
    (net (code "130") (name "Net-(PAD36-P)") (class "Default")
      (node (ref "E40") (pin "14") (pinfunction "14_14") (pintype "passive"))
      (node (ref "PAD36") (pin "1") (pinfunction "P_1") (pintype "passive"))
    )
    (net (code "131") (name "Net-(PAD37-P)") (class "Default")
      (node (ref "E40") (pin "13") (pinfunction "13_13") (pintype "passive"))
      (node (ref "PAD37") (pin "1") (pinfunction "P_1") (pintype "passive"))
    )
    (net (code "132") (name "Net-(PAD38-P)") (class "Default")
      (node (ref "E40") (pin "12") (pinfunction "12_12") (pintype "passive"))
      (node (ref "PAD38") (pin "1") (pinfunction "P_1") (pintype "passive"))
    )
    (net (code "133") (name "Net-(PAD39-P)") (class "Default")
      (node (ref "E40") (pin "11") (pinfunction "11_11") (pintype "passive"))
      (node (ref "PAD39") (pin "1") (pinfunction "P_1") (pintype "passive"))
    )
    (net (code "134") (name "Net-(PAD40-P)") (class "Default")
      (node (ref "E40") (pin "10") (pinfunction "10_10") (pintype "passive"))
      (node (ref "PAD40") (pin "1") (pinfunction "P_1") (pintype "passive"))
    )
    (net (code "135") (name "Net-(PAD41-P)") (class "Default")
      (node (ref "E40") (pin "9") (pinfunction "9_9") (pintype "passive"))
      (node (ref "PAD41") (pin "1") (pinfunction "P_1") (pintype "passive"))
    )
    (net (code "136") (name "Net-(PAD42-P)") (class "Default")
      (node (ref "E39") (pin "1") (pinfunction "1_1") (pintype "passive"))
      (node (ref "PAD42") (pin "1") (pinfunction "P_1") (pintype "passive"))
    )
    (net (code "137") (name "Net-(PAD43-P)") (class "Default")
      (node (ref "E39") (pin "2") (pinfunction "2_2") (pintype "passive"))
      (node (ref "PAD43") (pin "1") (pinfunction "P_1") (pintype "passive"))
    )
    (net (code "138") (name "Net-(PAD44-P)") (class "Default")
      (node (ref "E39") (pin "3") (pinfunction "3_3") (pintype "passive"))
      (node (ref "PAD44") (pin "1") (pinfunction "P_1") (pintype "passive"))
    )
    (net (code "139") (name "Net-(PAD45-P)") (class "Default")
      (node (ref "E39") (pin "4") (pinfunction "4_4") (pintype "passive"))
      (node (ref "PAD45") (pin "1") (pinfunction "P_1") (pintype "passive"))
    )
    (net (code "140") (name "Net-(PAD46-P)") (class "Default")
      (node (ref "E39") (pin "5") (pinfunction "5_5") (pintype "passive"))
      (node (ref "PAD46") (pin "1") (pinfunction "P_1") (pintype "passive"))
    )
    (net (code "141") (name "Net-(PAD47-P)") (class "Default")
      (node (ref "E39") (pin "6") (pinfunction "6_6") (pintype "passive"))
      (node (ref "PAD47") (pin "1") (pinfunction "P_1") (pintype "passive"))
    )
    (net (code "142") (name "Net-(PAD48-P)") (class "Default")
      (node (ref "E39") (pin "7") (pinfunction "7_7") (pintype "passive"))
      (node (ref "PAD48") (pin "1") (pinfunction "P_1") (pintype "passive"))
    )
    (net (code "143") (name "Net-(PAD49-P)") (class "Default")
      (node (ref "E39") (pin "8") (pinfunction "8_8") (pintype "passive"))
      (node (ref "PAD49") (pin "1") (pinfunction "P_1") (pintype "passive"))
    )
    (net (code "144") (name "Net-(PAD50-P)") (class "Default")
      (node (ref "E39") (pin "16") (pinfunction "16_16") (pintype "passive"))
      (node (ref "PAD50") (pin "1") (pinfunction "P_1") (pintype "passive"))
    )
    (net (code "145") (name "Net-(PAD51-P)") (class "Default")
      (node (ref "E39") (pin "15") (pinfunction "15_15") (pintype "passive"))
      (node (ref "PAD51") (pin "1") (pinfunction "P_1") (pintype "passive"))
    )
    (net (code "146") (name "Net-(PAD52-P)") (class "Default")
      (node (ref "E39") (pin "14") (pinfunction "14_14") (pintype "passive"))
      (node (ref "PAD52") (pin "1") (pinfunction "P_1") (pintype "passive"))
    )
    (net (code "147") (name "Net-(PAD53-P)") (class "Default")
      (node (ref "E39") (pin "13") (pinfunction "13_13") (pintype "passive"))
      (node (ref "PAD53") (pin "1") (pinfunction "P_1") (pintype "passive"))
    )
    (net (code "148") (name "Net-(PAD54-P)") (class "Default")
      (node (ref "E39") (pin "12") (pinfunction "12_12") (pintype "passive"))
      (node (ref "PAD54") (pin "1") (pinfunction "P_1") (pintype "passive"))
    )
    (net (code "149") (name "Net-(PAD55-P)") (class "Default")
      (node (ref "E39") (pin "11") (pinfunction "11_11") (pintype "passive"))
      (node (ref "PAD55") (pin "1") (pinfunction "P_1") (pintype "passive"))
    )
    (net (code "150") (name "Net-(PAD56-P)") (class "Default")
      (node (ref "E39") (pin "10") (pinfunction "10_10") (pintype "passive"))
      (node (ref "PAD56") (pin "1") (pinfunction "P_1") (pintype "passive"))
    )
    (net (code "151") (name "Net-(PAD57-P)") (class "Default")
      (node (ref "E39") (pin "9") (pinfunction "9_9") (pintype "passive"))
      (node (ref "PAD57") (pin "1") (pinfunction "P_1") (pintype "passive"))
    )
    (net (code "152") (name "PARITY") (class "Default")
      (node (ref "E15") (pin "1") (pinfunction "I0_1") (pintype "input"))
      (node (ref "E15") (pin "13") (pinfunction "I1_13") (pintype "input"))
      (node (ref "E15") (pin "2") (pinfunction "I1_2") (pintype "input"))
      (node (ref "E4") (pin "15") (pinfunction "RCO_15") (pintype "output"))
    )
    (net (code "153") (name "RD") (class "Default")
      (node (ref "E25") (pin "1") (pinfunction "I_1") (pintype "input"))
      (node (ref "E32") (pin "10") (pinfunction "I1_10") (pintype "input"))
      (node (ref "E35") (pin "10") (pinfunction "O_10") (pintype "output"))
    )
    (net (code "154") (name "RUN") (class "Default")
      (node (ref "E18") (pin "11") (pinfunction "I0_11") (pintype "input"))
      (node (ref "E30") (pin "9") (pinfunction "Q_9") (pintype "output"))
      (node (ref "IC9") (pin "6") (pinfunction "I0_6") (pintype "input"))
      (node (ref "IC9") (pin "7") (pinfunction "I1_7") (pintype "input"))
    )
    (net (code "155") (name "RX_DATA") (class "Default")
      (node (ref "E22") (pin "2") (pinfunction "J_2") (pintype "input"))
      (node (ref "E22") (pin "3") (pinfunction "K_3") (pintype "input"))
      (node (ref "E35") (pin "1") (pinfunction "O_1") (pintype "output"))
    )
    (net (code "156") (name "SHIFT") (class "Default")
      (node (ref "E32") (pin "3") (pinfunction "I0_3") (pintype "input"))
      (node (ref "E35") (pin "4") (pinfunction "O_4") (pintype "output"))
    )
    (net (code "157") (name "TR_SKIP") (class "Default")
      (node (ref "E18") (pin "1") (pinfunction "O_1") (pintype "output"))
      (node (ref "E20") (pin "1") (pinfunction "I0_1") (pintype "input"))
      (node (ref "E26") (pin "2") (pinfunction "I1_2") (pintype "input"))
    )
    (net (code "158") (name "VCC") (class "Default")
      (node (ref "C1") (pin "1") (pinfunction "1_1") (pintype "passive"))
      (node (ref "C10") (pin "1") (pinfunction "1_1") (pintype "passive"))
      (node (ref "C11") (pin "1") (pinfunction "1_1") (pintype "passive"))
      (node (ref "C12") (pin "1") (pinfunction "1_1") (pintype "passive"))
      (node (ref "C13") (pin "1") (pinfunction "1_1") (pintype "passive"))
      (node (ref "C14") (pin "1") (pinfunction "1_1") (pintype "passive"))
      (node (ref "C15") (pin "1") (pinfunction "1_1") (pintype "passive"))
      (node (ref "C16") (pin "1") (pinfunction "1_1") (pintype "passive"))
      (node (ref "C17") (pin "1") (pinfunction "1_1") (pintype "passive"))
      (node (ref "C18") (pin "1") (pinfunction "1_1") (pintype "passive"))
      (node (ref "C19") (pin "1") (pinfunction "1_1") (pintype "passive"))
      (node (ref "C2") (pin "1") (pinfunction "1_1") (pintype "passive"))
      (node (ref "C20") (pin "1") (pinfunction "1_1") (pintype "passive"))
      (node (ref "C21") (pin "1") (pinfunction "1_1") (pintype "passive"))
      (node (ref "C22") (pin "1") (pinfunction "1_1") (pintype "passive"))
      (node (ref "C23") (pin "1") (pinfunction "1_1") (pintype "passive"))
      (node (ref "C24") (pin "1") (pinfunction "1_1") (pintype "passive"))
      (node (ref "C25") (pin "1") (pinfunction "1_1") (pintype "passive"))
      (node (ref "C26") (pin "1") (pinfunction "1_1") (pintype "passive"))
      (node (ref "C27") (pin "1") (pinfunction "1_1") (pintype "passive"))
      (node (ref "C28") (pin "1") (pinfunction "1_1") (pintype "passive"))
      (node (ref "C29") (pin "1") (pinfunction "1_1") (pintype "passive"))
      (node (ref "C3") (pin "1") (pinfunction "1_1") (pintype "passive"))
      (node (ref "C30") (pin "1") (pinfunction "1_1") (pintype "passive"))
      (node (ref "C31") (pin "1") (pinfunction "1_1") (pintype "passive"))
      (node (ref "C32") (pin "1") (pinfunction "1_1") (pintype "passive"))
      (node (ref "C33") (pin "1") (pinfunction "1_1") (pintype "passive"))
      (node (ref "C34") (pin "1") (pinfunction "1_1") (pintype "passive"))
      (node (ref "C35") (pin "1") (pinfunction "1_1") (pintype "passive"))
      (node (ref "C36") (pin "1") (pinfunction "1_1") (pintype "passive"))
      (node (ref "C37") (pin "1") (pinfunction "1_1") (pintype "passive"))
      (node (ref "C38") (pin "1") (pinfunction "1_1") (pintype "passive"))
      (node (ref "C39") (pin "1") (pinfunction "1_1") (pintype "passive"))
      (node (ref "C4") (pin "1") (pinfunction "1_1") (pintype "passive"))
      (node (ref "C40") (pin "+") (pinfunction "+_+") (pintype "passive"))
      (node (ref "C5") (pin "1") (pinfunction "1_1") (pintype "passive"))
      (node (ref "C6") (pin "1") (pinfunction "1_1") (pintype "passive"))
      (node (ref "C7") (pin "1") (pinfunction "1_1") (pintype "passive"))
      (node (ref "C8") (pin "1") (pinfunction "1_1") (pintype "passive"))
      (node (ref "C9") (pin "1") (pinfunction "1_1") (pintype "passive"))
      (node (ref "E1") (pin "4") (pinfunction "I1_4") (pintype "input"))
      (node (ref "E1") (pin "5") (pinfunction "I2_5") (pintype "input"))
      (node (ref "E14") (pin "6") (pinfunction "G1_6") (pintype "input"))
      (node (ref "E16") (pin "10") (pinfunction "PRE_10") (pintype "input"))
      (node (ref "E16") (pin "4") (pinfunction "PRE_4") (pintype "input"))
      (node (ref "E17") (pin "16") (pinfunction "K_16") (pintype "input"))
      (node (ref "E17") (pin "4") (pinfunction "J_4") (pintype "input"))
      (node (ref "E17") (pin "7") (pinfunction "PRE_7") (pintype "input"))
      (node (ref "E19") (pin "12") (pinfunction "K_12") (pintype "input"))
      (node (ref "E19") (pin "16") (pinfunction "K_16") (pintype "input"))
      (node (ref "E19") (pin "4") (pinfunction "J_4") (pintype "input"))
      (node (ref "E19") (pin "9") (pinfunction "J_9") (pintype "input"))
      (node (ref "E2") (pin "10") (pinfunction "PRE_10") (pintype "input"))
      (node (ref "E2") (pin "11") (pinfunction "CLK_11") (pintype "input"))
      (node (ref "E2") (pin "12") (pinfunction "D_12") (pintype "input"))
      (node (ref "E2") (pin "13") (pinfunction "CLR_13") (pintype "input"))
      (node (ref "E20") (pin "10") (pinfunction "I1_10") (pintype "input"))
      (node (ref "E20") (pin "9") (pinfunction "I0_9") (pintype "input"))
      (node (ref "E25") (pin "11") (pinfunction "I_11") (pintype "input"))
      (node (ref "E25") (pin "13") (pinfunction "I_13") (pintype "input"))
      (node (ref "E30") (pin "10") (pinfunction "PRE_10") (pintype "input"))
      (node (ref "E30") (pin "12") (pinfunction "D_12") (pintype "input"))
      (node (ref "E30") (pin "4") (pinfunction "PRE_4") (pintype "input"))
      (node (ref "R1") (pin "2") (pinfunction "2_2") (pintype "passive"))
      (node (ref "R18") (pin "2") (pinfunction "2_2") (pintype "passive"))
      (node (ref "R19") (pin "1") (pinfunction "1_1") (pintype "passive"))
      (node (ref "R2") (pin "2") (pinfunction "2_2") (pintype "passive"))
      (node (ref "R20") (pin "2") (pinfunction "2_2") (pintype "passive"))
      (node (ref "R3") (pin "2") (pinfunction "2_2") (pintype "passive"))
      (node (ref "R4") (pin "2") (pinfunction "2_2") (pintype "passive"))
      (node (ref "R5") (pin "2") (pinfunction "2_2") (pintype "passive"))
      (node (ref "R6") (pin "2") (pinfunction "2_2") (pintype "passive"))
      (node (ref "R7") (pin "2") (pinfunction "2_2") (pintype "passive"))
      (node (ref "R8") (pin "2") (pinfunction "2_2") (pintype "passive"))
      (node (ref "R9") (pin "2") (pinfunction "2_2") (pintype "passive"))
      (node (ref "SL1") (pin "1") (pinfunction "S_1") (pintype "passive"))
    )
    (net (code "159") (name "WRT") (class "Default")
      (node (ref "E10") (pin "5") (pinfunction "I2_5") (pintype "input"))
      (node (ref "E15") (pin "10") (pinfunction "I1_10") (pintype "input"))
      (node (ref "E25") (pin "2") (pinfunction "O_2") (pintype "output"))
      (node (ref "IC7") (pin "6") (pinfunction "I0_6") (pintype "input"))
    )
    (net (code "160") (name "XDR2") (class "Default")
      (node (ref "E10") (pin "2") (pinfunction "I1_2") (pintype "input"))
      (node (ref "E5") (pin "12") (pinfunction "I0_12") (pintype "input"))
      (node (ref "E5") (pin "8") (pinfunction "O_8") (pintype "output"))
    )
    (net (code "161") (name "XFER_REQ") (class "Default")
      (node (ref "E20") (pin "12") (pinfunction "I0_12") (pintype "input"))
      (node (ref "E26") (pin "1") (pinfunction "I0_1") (pintype "input"))
      (node (ref "E36") (pin "4") (pinfunction "O_4") (pintype "output"))
    )
    (net (code "162") (name "unconnected-(D34L1-2-PadB)") (class "Default")
      (node (ref "D34L1") (pin "B") (pinfunction "2_B") (pintype "bidirectional"))
    )
    (net (code "163") (name "unconnected-(D34L1-34-PadNN)") (class "Default")
      (node (ref "D34L1") (pin "NN") (pinfunction "34_NN") (pintype "bidirectional"))
    )
    (net (code "164") (name "unconnected-(D34L1-38-PadTT)") (class "Default")
      (node (ref "D34L1") (pin "TT") (pinfunction "38_TT") (pintype "bidirectional"))
    )
    (net (code "165") (name "unconnected-(D34L1-40-PadVV)") (class "Default")
      (node (ref "D34L1") (pin "VV") (pinfunction "40_VV") (pintype "bidirectional"))
    )
    (net (code "166") (name "unconnected-(D34L2-2-PadB)") (class "Default")
      (node (ref "D34L2") (pin "B") (pinfunction "2_B") (pintype "bidirectional"))
    )
    (net (code "167") (name "unconnected-(D34L2-34-PadNN)") (class "Default")
      (node (ref "D34L2") (pin "NN") (pinfunction "34_NN") (pintype "bidirectional"))
    )
    (net (code "168") (name "unconnected-(D34L2-38-PadTT)") (class "Default")
      (node (ref "D34L2") (pin "TT") (pinfunction "38_TT") (pintype "bidirectional"))
    )
    (net (code "169") (name "unconnected-(D34L2-40-PadVV)") (class "Default")
      (node (ref "D34L2") (pin "VV") (pinfunction "40_VV") (pintype "bidirectional"))
    )
    (net (code "170") (name "unconnected-(D35L1-2-PadB)") (class "Default")
      (node (ref "D35L1") (pin "B") (pinfunction "2_B") (pintype "bidirectional"))
    )
    (net (code "171") (name "unconnected-(D35L1-40-PadVV)") (class "Default")
      (node (ref "D35L1") (pin "VV") (pinfunction "40_VV") (pintype "bidirectional"))
    )
    (net (code "172") (name "unconnected-(D35L2-2-PadB)") (class "Default")
      (node (ref "D35L2") (pin "B") (pinfunction "2_B") (pintype "bidirectional"))
    )
    (net (code "173") (name "unconnected-(D35L2-40-PadVV)") (class "Default")
      (node (ref "D35L2") (pin "VV") (pinfunction "40_VV") (pintype "bidirectional"))
    )
    (net (code "174") (name "unconnected-(D36L1-2-PadB)") (class "Default")
      (node (ref "D36L1") (pin "B") (pinfunction "2_B") (pintype "bidirectional"))
    )
    (net (code "175") (name "unconnected-(D36L1-40-PadVV)") (class "Default")
      (node (ref "D36L1") (pin "VV") (pinfunction "40_VV") (pintype "bidirectional"))
    )
    (net (code "176") (name "unconnected-(D36L2-2-PadB)") (class "Default")
      (node (ref "D36L2") (pin "B") (pinfunction "2_B") (pintype "bidirectional"))
    )
    (net (code "177") (name "unconnected-(D36L2-40-PadVV)") (class "Default")
      (node (ref "D36L2") (pin "VV") (pinfunction "40_VV") (pintype "bidirectional"))
    )
    (net (code "178") (name "unconnected-(E2A-Q-Pad5)") (class "Default")
      (node (ref "E2") (pin "5") (pinfunction "Q_5") (pintype "output"))
    )
    (net (code "179") (name "unconnected-(E2B-Q-Pad9)") (class "Default")
      (node (ref "E2") (pin "9") (pinfunction "Q_9") (pintype "output"))
    )
    (net (code "180") (name "unconnected-(E2B-~{Q}-Pad8)") (class "Default")
      (node (ref "E2") (pin "8") (pinfunction "~{Q}_8") (pintype "output"))
    )
    (net (code "181") (name "unconnected-(E4A-QA-Pad14)") (class "Default")
      (node (ref "E4") (pin "14") (pinfunction "QA_14") (pintype "output"))
    )
    (net (code "182") (name "unconnected-(E4A-QB-Pad13)") (class "Default")
      (node (ref "E4") (pin "13") (pinfunction "QB_13") (pintype "output"))
    )
    (net (code "183") (name "unconnected-(E4A-QC-Pad12)") (class "Default")
      (node (ref "E4") (pin "12") (pinfunction "QC_12") (pintype "output"))
    )
    (net (code "184") (name "unconnected-(E4A-QD-Pad11)") (class "Default")
      (node (ref "E4") (pin "11") (pinfunction "QD_11") (pintype "output"))
    )
    (net (code "185") (name "unconnected-(E11A-Y0-Pad15)") (class "Default")
      (node (ref "E11") (pin "15") (pinfunction "Y0_15") (pintype "output"))
    )
    (net (code "186") (name "unconnected-(E11A-Y2-Pad13)") (class "Default")
      (node (ref "E11") (pin "13") (pinfunction "Y2_13") (pintype "output"))
    )
    (net (code "187") (name "unconnected-(E11A-Y3-Pad12)") (class "Default")
      (node (ref "E11") (pin "12") (pinfunction "Y3_12") (pintype "output"))
    )
    (net (code "188") (name "unconnected-(E11A-Y4-Pad11)") (class "Default")
      (node (ref "E11") (pin "11") (pinfunction "Y4_11") (pintype "output"))
    )
    (net (code "189") (name "unconnected-(E11A-Y5-Pad10)") (class "Default")
      (node (ref "E11") (pin "10") (pinfunction "Y5_10") (pintype "output"))
    )
    (net (code "190") (name "unconnected-(E11A-Y6-Pad9)") (class "Default")
      (node (ref "E11") (pin "9") (pinfunction "Y6_9") (pintype "output"))
    )
    (net (code "191") (name "unconnected-(E12A-Y0-Pad15)") (class "Default")
      (node (ref "E12") (pin "15") (pinfunction "Y0_15") (pintype "output"))
    )
    (net (code "192") (name "unconnected-(E12A-Y1-Pad14)") (class "Default")
      (node (ref "E12") (pin "14") (pinfunction "Y1_14") (pintype "output"))
    )
    (net (code "193") (name "unconnected-(E12A-Y4-Pad11)") (class "Default")
      (node (ref "E12") (pin "11") (pinfunction "Y4_11") (pintype "output"))
    )
    (net (code "194") (name "unconnected-(E12A-Y5-Pad10)") (class "Default")
      (node (ref "E12") (pin "10") (pinfunction "Y5_10") (pintype "output"))
    )
    (net (code "195") (name "unconnected-(E12A-Y6-Pad9)") (class "Default")
      (node (ref "E12") (pin "9") (pinfunction "Y6_9") (pintype "output"))
    )
    (net (code "196") (name "unconnected-(E12A-Y7-Pad7)") (class "Default")
      (node (ref "E12") (pin "7") (pinfunction "Y7_7") (pintype "output"))
    )
    (net (code "197") (name "unconnected-(E13A-Y0-Pad15)") (class "Default")
      (node (ref "E13") (pin "15") (pinfunction "Y0_15") (pintype "output"))
    )
    (net (code "198") (name "unconnected-(E13A-Y1-Pad14)") (class "Default")
      (node (ref "E13") (pin "14") (pinfunction "Y1_14") (pintype "output"))
    )
    (net (code "199") (name "unconnected-(E13A-Y2-Pad13)") (class "Default")
      (node (ref "E13") (pin "13") (pinfunction "Y2_13") (pintype "output"))
    )
    (net (code "200") (name "unconnected-(E13A-Y3-Pad12)") (class "Default")
      (node (ref "E13") (pin "12") (pinfunction "Y3_12") (pintype "output"))
    )
    (net (code "201") (name "unconnected-(E17B-Q-Pad11)") (class "Default")
      (node (ref "E17") (pin "11") (pinfunction "Q_11") (pintype "output"))
    )
    (net (code "202") (name "unconnected-(E19A-Q-Pad15)") (class "Default")
      (node (ref "E19") (pin "15") (pinfunction "Q_15") (pintype "output"))
    )
    (net (code "203") (name "unconnected-(E19B-Q-Pad11)") (class "Default")
      (node (ref "E19") (pin "11") (pinfunction "Q_11") (pintype "output"))
    )
    (net (code "204") (name "unconnected-(E20C-O-Pad8)") (class "Default")
      (node (ref "E20") (pin "8") (pinfunction "O_8") (pintype "output"))
    )
    (net (code "205") (name "unconnected-(E21A-~{QD}-Pad11)") (class "Default")
      (node (ref "E21") (pin "11") (pinfunction "~{QD}_11") (pintype "output"))
    )
    (net (code "206") (name "unconnected-(E22A-~{QD}-Pad11)") (class "Default")
      (node (ref "E22") (pin "11") (pinfunction "~{QD}_11") (pintype "output"))
    )
    (net (code "207") (name "unconnected-(E23A-~{QD}-Pad11)") (class "Default")
      (node (ref "E23") (pin "11") (pinfunction "~{QD}_11") (pintype "output"))
    )
    (net (code "208") (name "unconnected-(E26D-O-Pad11)") (class "Default")
      (node (ref "E26") (pin "11") (pinfunction "O_11") (pintype "output"))
    )
    (net (code "209") (name "unconnected-(E30A-~{Q}-Pad6)") (class "Default")
      (node (ref "E30") (pin "6") (pinfunction "~{Q}_6") (pintype "output"))
    )
    (net (code "210") (name "unconnected-(E30B-~{Q}-Pad8)") (class "Default")
      (node (ref "E30") (pin "8") (pinfunction "~{Q}_8") (pintype "output"))
    )
    (net (code "211") (name "unconnected-(E36D-O-Pad13)") (class "Default")
      (node (ref "E36") (pin "13") (pinfunction "O_13") (pintype "output"))
    )
    (net (code "212") (name "unconnected-(LASTDEV-Pad8)") (class "Default")
      (node (ref "LASTDEV") (pin "8") (pinfunction "8_8") (pintype "passive"))
    )
    (net (code "213") (name "unconnected-(LASTDEV-Pad9)") (class "Default")
      (node (ref "LASTDEV") (pin "9") (pinfunction "9_9") (pintype "passive"))
    )
    (net (code "214") (name "unconnected-(LASTDEV-Pad10)") (class "Default")
      (node (ref "LASTDEV") (pin "10") (pinfunction "10_10") (pintype "passive"))
    )
    (net (code "215") (name "~{ACB00}") (class "Default")
      (node (ref "D34L1") (pin "D") (pinfunction "4_D") (pintype "bidirectional"))
      (node (ref "D34L2") (pin "D") (pinfunction "4_D") (pintype "bidirectional"))
      (node (ref "IC6") (pin "3") (pinfunction "O_3") (pintype "open_collector"))
    )
    (net (code "216") (name "~{ACB01}") (class "Default")
      (node (ref "D34L1") (pin "J") (pinfunction "8_J") (pintype "bidirectional"))
      (node (ref "D34L2") (pin "J") (pinfunction "8_J") (pintype "bidirectional"))
      (node (ref "IC6") (pin "5") (pinfunction "O_5") (pintype "open_collector"))
    )
    (net (code "217") (name "~{ACB02}") (class "Default")
      (node (ref "D34L1") (pin "N") (pinfunction "12_N") (pintype "bidirectional"))
      (node (ref "D34L2") (pin "N") (pinfunction "12_N") (pintype "bidirectional"))
      (node (ref "IC1") (pin "3") (pinfunction "O_3") (pintype "open_collector"))
    )
    (net (code "218") (name "~{ACB03}") (class "Default")
      (node (ref "D34L1") (pin "T") (pinfunction "16_T") (pintype "bidirectional"))
      (node (ref "D34L2") (pin "T") (pinfunction "16_T") (pintype "bidirectional"))
      (node (ref "IC2") (pin "5") (pinfunction "O_5") (pintype "open_collector"))
    )
    (net (code "219") (name "~{ACB04}") (class "Default")
      (node (ref "D34L1") (pin "X") (pinfunction "20_X") (pintype "bidirectional"))
      (node (ref "D34L2") (pin "X") (pinfunction "20_X") (pintype "bidirectional"))
      (node (ref "IC1") (pin "5") (pinfunction "O_5") (pintype "open_collector"))
    )
    (net (code "220") (name "~{ACB05}") (class "Default")
      (node (ref "D34L1") (pin "BB") (pinfunction "24_BB") (pintype "bidirectional"))
      (node (ref "D34L2") (pin "BB") (pinfunction "24_BB") (pintype "bidirectional"))
      (node (ref "IC4") (pin "3") (pinfunction "O_3") (pintype "open_collector"))
    )
    (net (code "221") (name "~{ACB06}") (class "Default")
      (node (ref "D34L1") (pin "FF") (pinfunction "28_FF") (pintype "bidirectional"))
      (node (ref "D34L2") (pin "FF") (pinfunction "28_FF") (pintype "bidirectional"))
      (node (ref "IC3") (pin "3") (pinfunction "O_3") (pintype "open_collector"))
    )
    (net (code "222") (name "~{ACB07}") (class "Default")
      (node (ref "D34L1") (pin "LL") (pinfunction "32_LL") (pintype "bidirectional"))
      (node (ref "D34L2") (pin "LL") (pinfunction "32_LL") (pintype "bidirectional"))
      (node (ref "IC3") (pin "5") (pinfunction "O_5") (pintype "open_collector"))
    )
    (net (code "223") (name "~{ACB08}") (class "Default")
      (node (ref "D34L1") (pin "RR") (pinfunction "36_RR") (pintype "bidirectional"))
      (node (ref "D34L2") (pin "RR") (pinfunction "36_RR") (pintype "bidirectional"))
      (node (ref "IC4") (pin "5") (pinfunction "O_5") (pintype "open_collector"))
    )
    (net (code "224") (name "~{ACB09}") (class "Default")
      (node (ref "D34L1") (pin "F") (pinfunction "6_F") (pintype "bidirectional"))
      (node (ref "D34L2") (pin "F") (pinfunction "6_F") (pintype "bidirectional"))
      (node (ref "IC5") (pin "3") (pinfunction "O_3") (pintype "open_collector"))
    )
    (net (code "225") (name "~{ACB10}") (class "Default")
      (node (ref "D34L1") (pin "L") (pinfunction "10_L") (pintype "bidirectional"))
      (node (ref "D34L2") (pin "L") (pinfunction "10_L") (pintype "bidirectional"))
      (node (ref "IC5") (pin "5") (pinfunction "O_5") (pintype "open_collector"))
    )
    (net (code "226") (name "~{ACB11}") (class "Default")
      (node (ref "D34L1") (pin "R") (pinfunction "14_R") (pintype "bidirectional"))
      (node (ref "D34L2") (pin "R") (pinfunction "14_R") (pintype "bidirectional"))
      (node (ref "IC2") (pin "3") (pinfunction "O_3") (pintype "open_collector"))
    )
    (net (code "227") (name "~{ACCLEAR}") (class "Default")
      (node (ref "D34L1") (pin "DD") (pinfunction "26_DD") (pintype "bidirectional"))
      (node (ref "D34L2") (pin "DD") (pinfunction "26_DD") (pintype "bidirectional"))
      (node (ref "IC7") (pin "3") (pinfunction "O_3") (pintype "open_collector"))
    )
    (net (code "228") (name "~{BMB03}") (class "Default")
      (node (ref "D35L1") (pin "T") (pinfunction "16_T") (pintype "bidirectional"))
      (node (ref "D35L2") (pin "T") (pinfunction "16_T") (pintype "bidirectional"))
    )
    (net (code "229") (name "~{BMB04}") (class "Default")
      (node (ref "D35L1") (pin "BB") (pinfunction "24_BB") (pintype "bidirectional"))
      (node (ref "D35L2") (pin "BB") (pinfunction "24_BB") (pintype "bidirectional"))
    )
    (net (code "230") (name "~{BMB05}") (class "Default")
      (node (ref "D35L1") (pin "LL") (pinfunction "32_LL") (pintype "bidirectional"))
      (node (ref "D35L2") (pin "LL") (pinfunction "32_LL") (pintype "bidirectional"))
    )
    (net (code "231") (name "~{BMB06}") (class "Default")
      (node (ref "D35L1") (pin "F") (pinfunction "6_F") (pintype "bidirectional"))
      (node (ref "D35L2") (pin "F") (pinfunction "6_F") (pintype "bidirectional"))
    )
    (net (code "232") (name "~{BMB07}") (class "Default")
      (node (ref "D35L1") (pin "R") (pinfunction "14_R") (pintype "bidirectional"))
      (node (ref "D35L2") (pin "R") (pinfunction "14_R") (pintype "bidirectional"))
    )
    (net (code "233") (name "~{BMB08}") (class "Default")
      (node (ref "D35L1") (pin "Z") (pinfunction "22_Z") (pintype "bidirectional"))
      (node (ref "D35L2") (pin "Z") (pinfunction "22_Z") (pintype "bidirectional"))
    )
    (net (code "234") (name "~{BRUN}") (class "Default")
      (node (ref "D34L1") (pin "JJ") (pinfunction "30_JJ") (pintype "bidirectional"))
      (node (ref "D34L2") (pin "JJ") (pinfunction "30_JJ") (pintype "bidirectional"))
    )
    (net (code "235") (name "~{CLK_PARITY}") (class "Default")
      (node (ref "E17") (pin "6") (pinfunction "CLK_6") (pintype "input"))
      (node (ref "E32") (pin "6") (pinfunction "O_6") (pintype "output"))
      (node (ref "E5") (pin "4") (pinfunction "I0_4") (pintype "input"))
      (node (ref "E5") (pin "5") (pinfunction "I1_5") (pintype "input"))
    )
    (net (code "236") (name "~{DONE}") (class "Default")
      (node (ref "E10") (pin "4") (pinfunction "I1_4") (pintype "input"))
      (node (ref "E25") (pin "4") (pinfunction "O_4") (pintype "output"))
      (node (ref "E31") (pin "12") (pinfunction "I2_12") (pintype "input"))
    )
    (net (code "237") (name "~{ENB_BUF_LD}") (class "Default")
      (node (ref "E21") (pin "9") (pinfunction "S/~{L}_9") (pintype "input"))
      (node (ref "E22") (pin "9") (pinfunction "S/~{L}_9") (pintype "input"))
      (node (ref "E23") (pin "9") (pinfunction "S/~{L}_9") (pintype "input"))
      (node (ref "E24") (pin "11") (pinfunction "O_11") (pintype "output"))
      (node (ref "E32") (pin "13") (pinfunction "I2_13") (pintype "input"))
      (node (ref "E32") (pin "2") (pinfunction "I1_2") (pintype "input"))
      (node (ref "E4") (pin "9") (pinfunction "LD_9") (pintype "input"))
    )
    (net (code "238") (name "~{INIT1}") (class "Default")
      (node (ref "E11") (pin "7") (pinfunction "Y7_7") (pintype "output"))
      (node (ref "E2") (pin "4") (pinfunction "PRE_4") (pintype "input"))
    )
    (net (code "239") (name "~{INIT4}") (class "Default")
      (node (ref "E13") (pin "7") (pinfunction "Y7_7") (pintype "output"))
      (node (ref "E2") (pin "3") (pinfunction "CLK_3") (pintype "input"))
    )
    (net (code "240") (name "~{INIT}") (class "Default")
      (node (ref "E15") (pin "6") (pinfunction "O_6") (pintype "output"))
      (node (ref "E16") (pin "1") (pinfunction "CLR_1") (pintype "input"))
      (node (ref "E16") (pin "13") (pinfunction "CLR_13") (pintype "input"))
      (node (ref "E17") (pin "3") (pinfunction "CLR_3") (pintype "input"))
      (node (ref "E19") (pin "3") (pinfunction "CLR_3") (pintype "input"))
      (node (ref "E19") (pin "8") (pinfunction "CLR_8") (pintype "input"))
      (node (ref "E21") (pin "1") (pinfunction "CLR_1") (pintype "input"))
      (node (ref "E22") (pin "1") (pinfunction "CLR_1") (pintype "input"))
      (node (ref "E23") (pin "1") (pinfunction "CLR_1") (pintype "input"))
      (node (ref "E24") (pin "9") (pinfunction "I0_9") (pintype "input"))
      (node (ref "E30") (pin "1") (pinfunction "CLR_1") (pintype "input"))
      (node (ref "E4") (pin "1") (pinfunction "CLR_1") (pintype "input"))
    )
    (net (code "241") (name "~{INTR4}") (class "Default")
      (node (ref "E13") (pin "9") (pinfunction "Y6_9") (pintype "output"))
      (node (ref "E30") (pin "3") (pinfunction "CLK_3") (pintype "input"))
    )
    (net (code "242") (name "~{INT_RQ}") (class "Default")
      (node (ref "D34L1") (pin "Z") (pinfunction "22_Z") (pintype "bidirectional"))
      (node (ref "D34L2") (pin "Z") (pinfunction "22_Z") (pintype "bidirectional"))
      (node (ref "IC10") (pin "5") (pinfunction "O_5") (pintype "open_collector"))
    )
    (net (code "243") (name "~{IOS}") (class "Default")
      (node (ref "D34L1") (pin "V") (pinfunction "18_V") (pintype "bidirectional"))
      (node (ref "D34L2") (pin "V") (pinfunction "18_V") (pintype "bidirectional"))
      (node (ref "IC10") (pin "3") (pinfunction "O_3") (pintype "open_collector"))
    )
    (net (code "244") (name "~{LCD1}") (class "Default")
      (node (ref "E10") (pin "9") (pinfunction "I0_9") (pintype "input"))
      (node (ref "E11") (pin "14") (pinfunction "Y1_14") (pintype "output"))
      (node (ref "E16") (pin "11") (pinfunction "CLK_11") (pintype "input"))
      (node (ref "E16") (pin "3") (pinfunction "CLK_3") (pintype "input"))
      (node (ref "E24") (pin "5") (pinfunction "I1_5") (pintype "input"))
      (node (ref "E25") (pin "5") (pinfunction "I_5") (pintype "input"))
    )
    (net (code "245") (name "~{MAINT}") (class "Default")
      (node (ref "E10") (pin "3") (pinfunction "I0_3") (pintype "input"))
      (node (ref "E16") (pin "8") (pinfunction "~{Q}_8") (pintype "output"))
      (node (ref "E17") (pin "2") (pinfunction "PRE_2") (pintype "input"))
      (node (ref "E19") (pin "2") (pinfunction "PRE_2") (pintype "input"))
      (node (ref "E19") (pin "7") (pinfunction "PRE_7") (pintype "input"))
      (node (ref "E24") (pin "13") (pinfunction "I1_13") (pintype "input"))
      (node (ref "E31") (pin "10") (pinfunction "I1_10") (pintype "input"))
      (node (ref "E31") (pin "5") (pinfunction "I3_5") (pintype "input"))
      (node (ref "E31") (pin "9") (pinfunction "I0_9") (pintype "input"))
    )
    (net (code "246") (name "~{MYDEV}") (class "Default")
      (node (ref "E11") (pin "4") (pinfunction "G2A_4") (pintype "input"))
      (node (ref "E12") (pin "4") (pinfunction "G2A_4") (pintype "input"))
      (node (ref "E13") (pin "4") (pinfunction "G2A_4") (pintype "input"))
      (node (ref "IOT") (pin "1") (pinfunction "P_1") (pintype "passive"))
    )
    (net (code "247") (name "~{PARITY}") (class "Default")
      (node (ref "E15") (pin "12") (pinfunction "I0_12") (pintype "input"))
      (node (ref "E17") (pin "10") (pinfunction "~{Q}_10") (pintype "output"))
    )
    (net (code "248") (name "~{RX_12_BIT}") (class "Default")
      (node (ref "DRIVE") (pin "FF") (pinfunction "28_FF") (pintype "bidirectional"))
      (node (ref "IC8") (pin "3") (pinfunction "O_3") (pintype "open_collector"))
      (node (ref "R16") (pin "2") (pinfunction "2_2") (pintype "passive"))
      (node (ref "R7") (pin "1") (pinfunction "1_1") (pintype "passive"))
    )
    (net (code "249") (name "~{RX_DATA}") (class "Default")
      (node (ref "DRIVE") (pin "BB") (pinfunction "24_BB") (pintype "bidirectional"))
      (node (ref "E35") (pin "2") (pinfunction "I0_2") (pintype "input"))
      (node (ref "IC7") (pin "5") (pinfunction "O_5") (pintype "open_collector"))
      (node (ref "R17") (pin "2") (pinfunction "2_2") (pintype "passive"))
      (node (ref "R8") (pin "1") (pinfunction "1_1") (pintype "passive"))
    )
    (net (code "250") (name "~{RX_DONE}") (class "Default")
      (node (ref "DRIVE") (pin "X") (pinfunction "20_X") (pintype "bidirectional"))
      (node (ref "E36") (pin "8") (pinfunction "I0_8") (pintype "input"))
      (node (ref "R13") (pin "2") (pinfunction "2_2") (pintype "passive"))
      (node (ref "R4") (pin "1") (pinfunction "1_1") (pintype "passive"))
    )
    (net (code "251") (name "~{RX_ERROR}") (class "Default")
      (node (ref "DRIVE") (pin "J") (pinfunction "8_J") (pintype "bidirectional"))
      (node (ref "E36") (pin "3") (pinfunction "I1_3") (pintype "input"))
      (node (ref "R14") (pin "2") (pinfunction "2_2") (pintype "passive"))
      (node (ref "R5") (pin "1") (pinfunction "1_1") (pintype "passive"))
    )
    (net (code "252") (name "~{RX_INIT}") (class "Default")
      (node (ref "DRIVE") (pin "N") (pinfunction "12_N") (pintype "bidirectional"))
      (node (ref "IC8") (pin "5") (pinfunction "O_5") (pintype "open_collector"))
      (node (ref "R20") (pin "1") (pinfunction "1_1") (pintype "passive"))
      (node (ref "R9") (pin "1") (pinfunction "1_1") (pintype "passive"))
    )
    (net (code "253") (name "~{RX_OUT}") (class "Default")
      (node (ref "DRIVE") (pin "RR") (pinfunction "36_RR") (pintype "bidirectional"))
      (node (ref "E35") (pin "8") (pinfunction "I0_8") (pintype "input"))
      (node (ref "R12") (pin "2") (pinfunction "2_2") (pintype "passive"))
      (node (ref "R3") (pin "1") (pinfunction "1_1") (pintype "passive"))
    )
    (net (code "254") (name "~{RX_RUN}") (class "Default")
      (node (ref "DRIVE") (pin "D") (pinfunction "4_D") (pintype "bidirectional"))
      (node (ref "IC9") (pin "5") (pinfunction "O_5") (pintype "open_collector"))
      (node (ref "R15") (pin "2") (pinfunction "2_2") (pintype "passive"))
      (node (ref "R6") (pin "1") (pinfunction "1_1") (pintype "passive"))
    )
    (net (code "255") (name "~{RX_SHIFT}") (class "Default")
      (node (ref "DRIVE") (pin "LL") (pinfunction "32_LL") (pintype "bidirectional"))
      (node (ref "E35") (pin "5") (pinfunction "I0_5") (pintype "input"))
      (node (ref "R10") (pin "2") (pinfunction "2_2") (pintype "passive"))
      (node (ref "R2") (pin "1") (pinfunction "1_1") (pintype "passive"))
    )
    (net (code "256") (name "~{RX_TR_REQ}") (class "Default")
      (node (ref "DRIVE") (pin "T") (pinfunction "16_T") (pintype "bidirectional"))
      (node (ref "E36") (pin "5") (pinfunction "I0_5") (pintype "input"))
      (node (ref "R1") (pin "1") (pinfunction "1_1") (pintype "passive"))
      (node (ref "R11") (pin "2") (pinfunction "2_2") (pintype "passive"))
    )
    (net (code "257") (name "~{SDN4}") (class "Default")
      (node (ref "E13") (pin "10") (pinfunction "Y5_10") (pintype "output"))
      (node (ref "E18") (pin "8") (pinfunction "I0_8") (pintype "input"))
    )
    (net (code "258") (name "~{SER4}") (class "Default")
      (node (ref "E13") (pin "11") (pinfunction "Y4_11") (pintype "output"))
      (node (ref "E18") (pin "5") (pinfunction "I0_5") (pintype "input"))
    )
    (net (code "259") (name "~{STR2}") (class "Default")
      (node (ref "E12") (pin "12") (pinfunction "Y3_12") (pintype "output"))
      (node (ref "E18") (pin "2") (pinfunction "I0_2") (pintype "input"))
    )
    (net (code "260") (name "~{XDR2}") (class "Default")
      (node (ref "E12") (pin "13") (pinfunction "Y2_13") (pintype "output"))
      (node (ref "E24") (pin "4") (pinfunction "I0_4") (pintype "input"))
      (node (ref "E25") (pin "9") (pinfunction "I_9") (pintype "input"))
      (node (ref "E35") (pin "12") (pinfunction "I1_12") (pintype "input"))
      (node (ref "E5") (pin "10") (pinfunction "I1_10") (pintype "input"))
      (node (ref "E5") (pin "9") (pinfunction "I0_9") (pintype "input"))
    )
  )
)
